# ibz_bldc_drv_revA.net
KiCad netlist of a schematic drawn in EAGLE
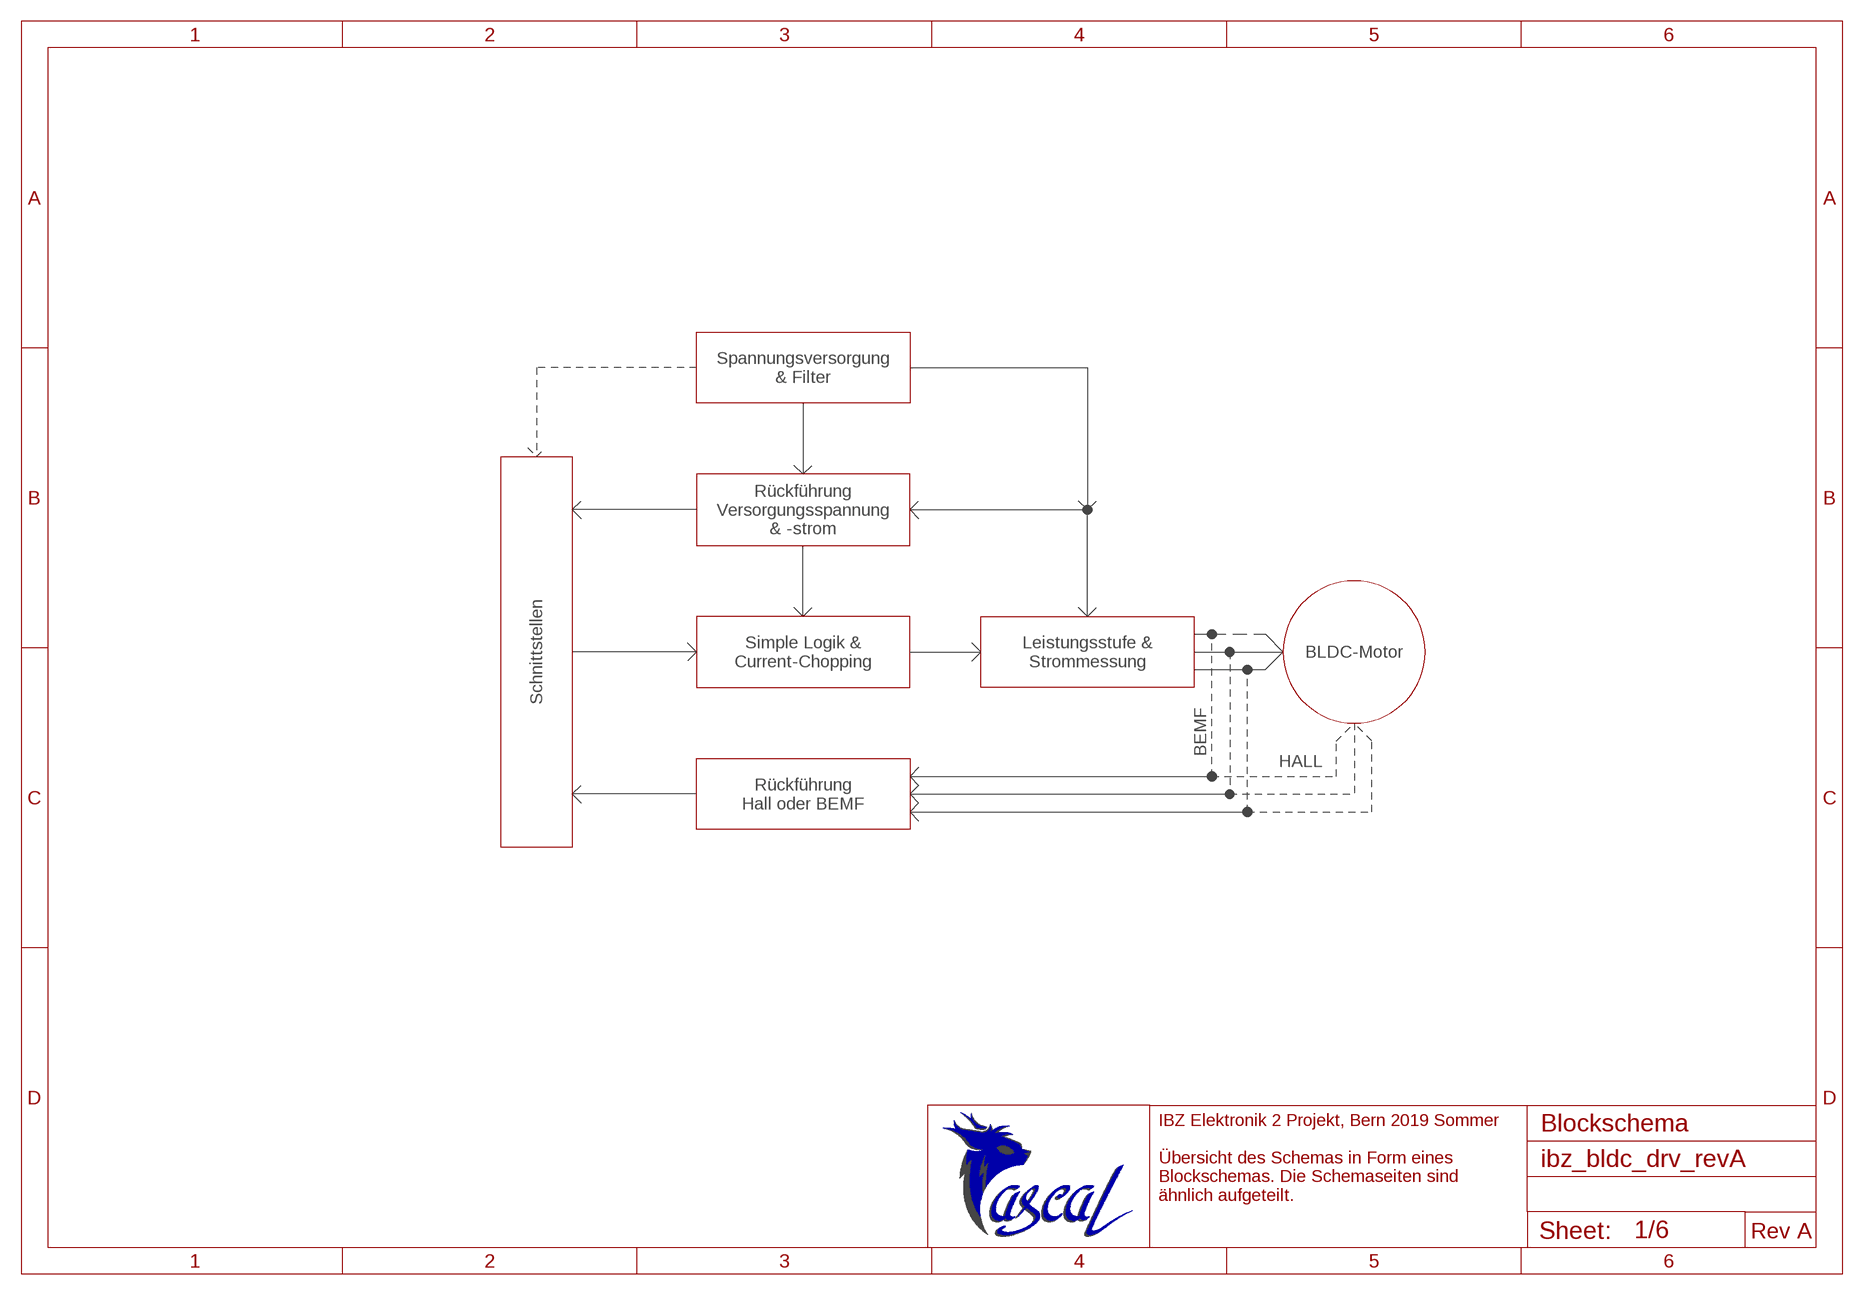
[diagram p0: schematic, sheet 1]
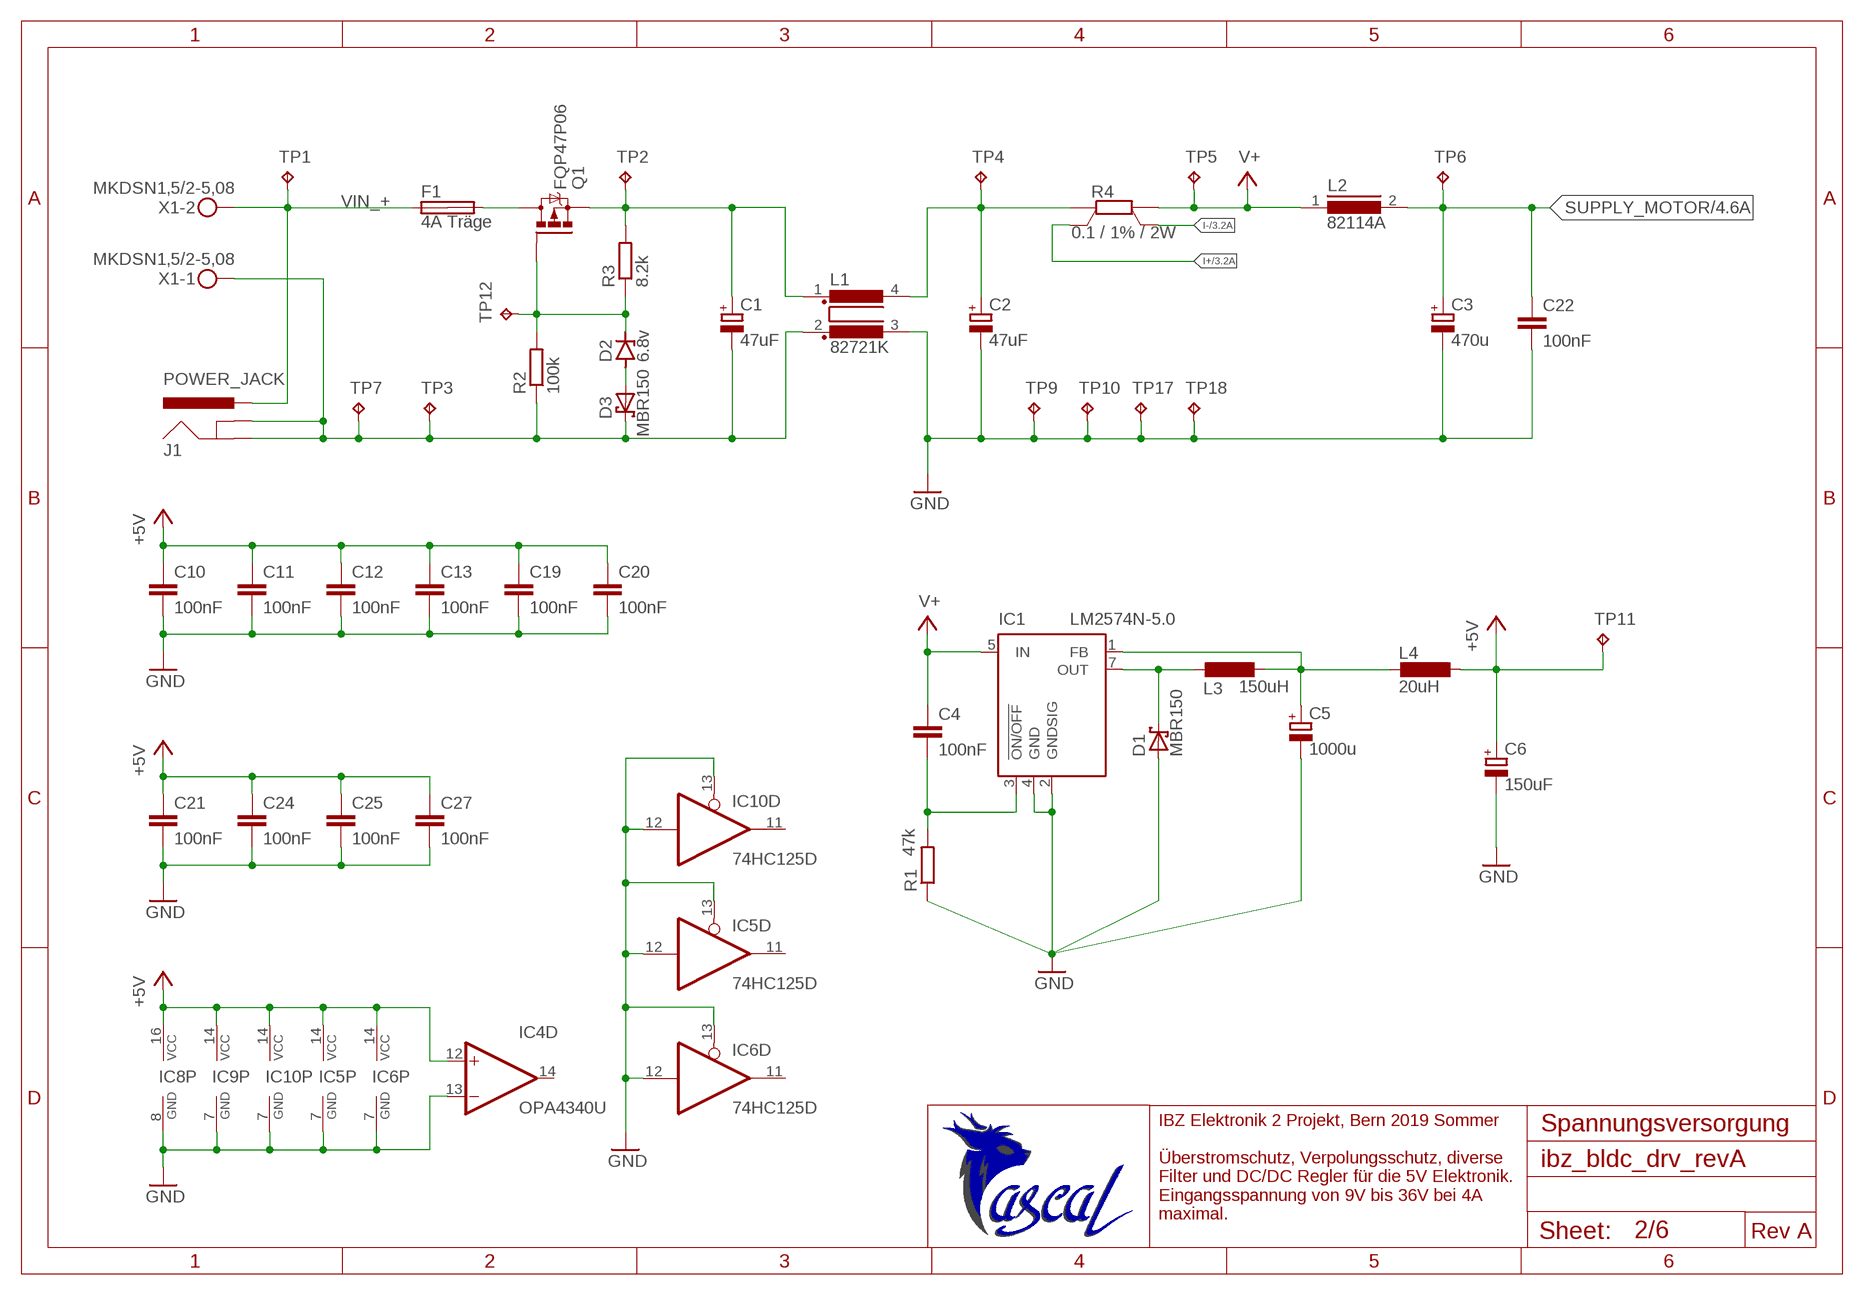
[diagram p1: schematic, sheet 2]
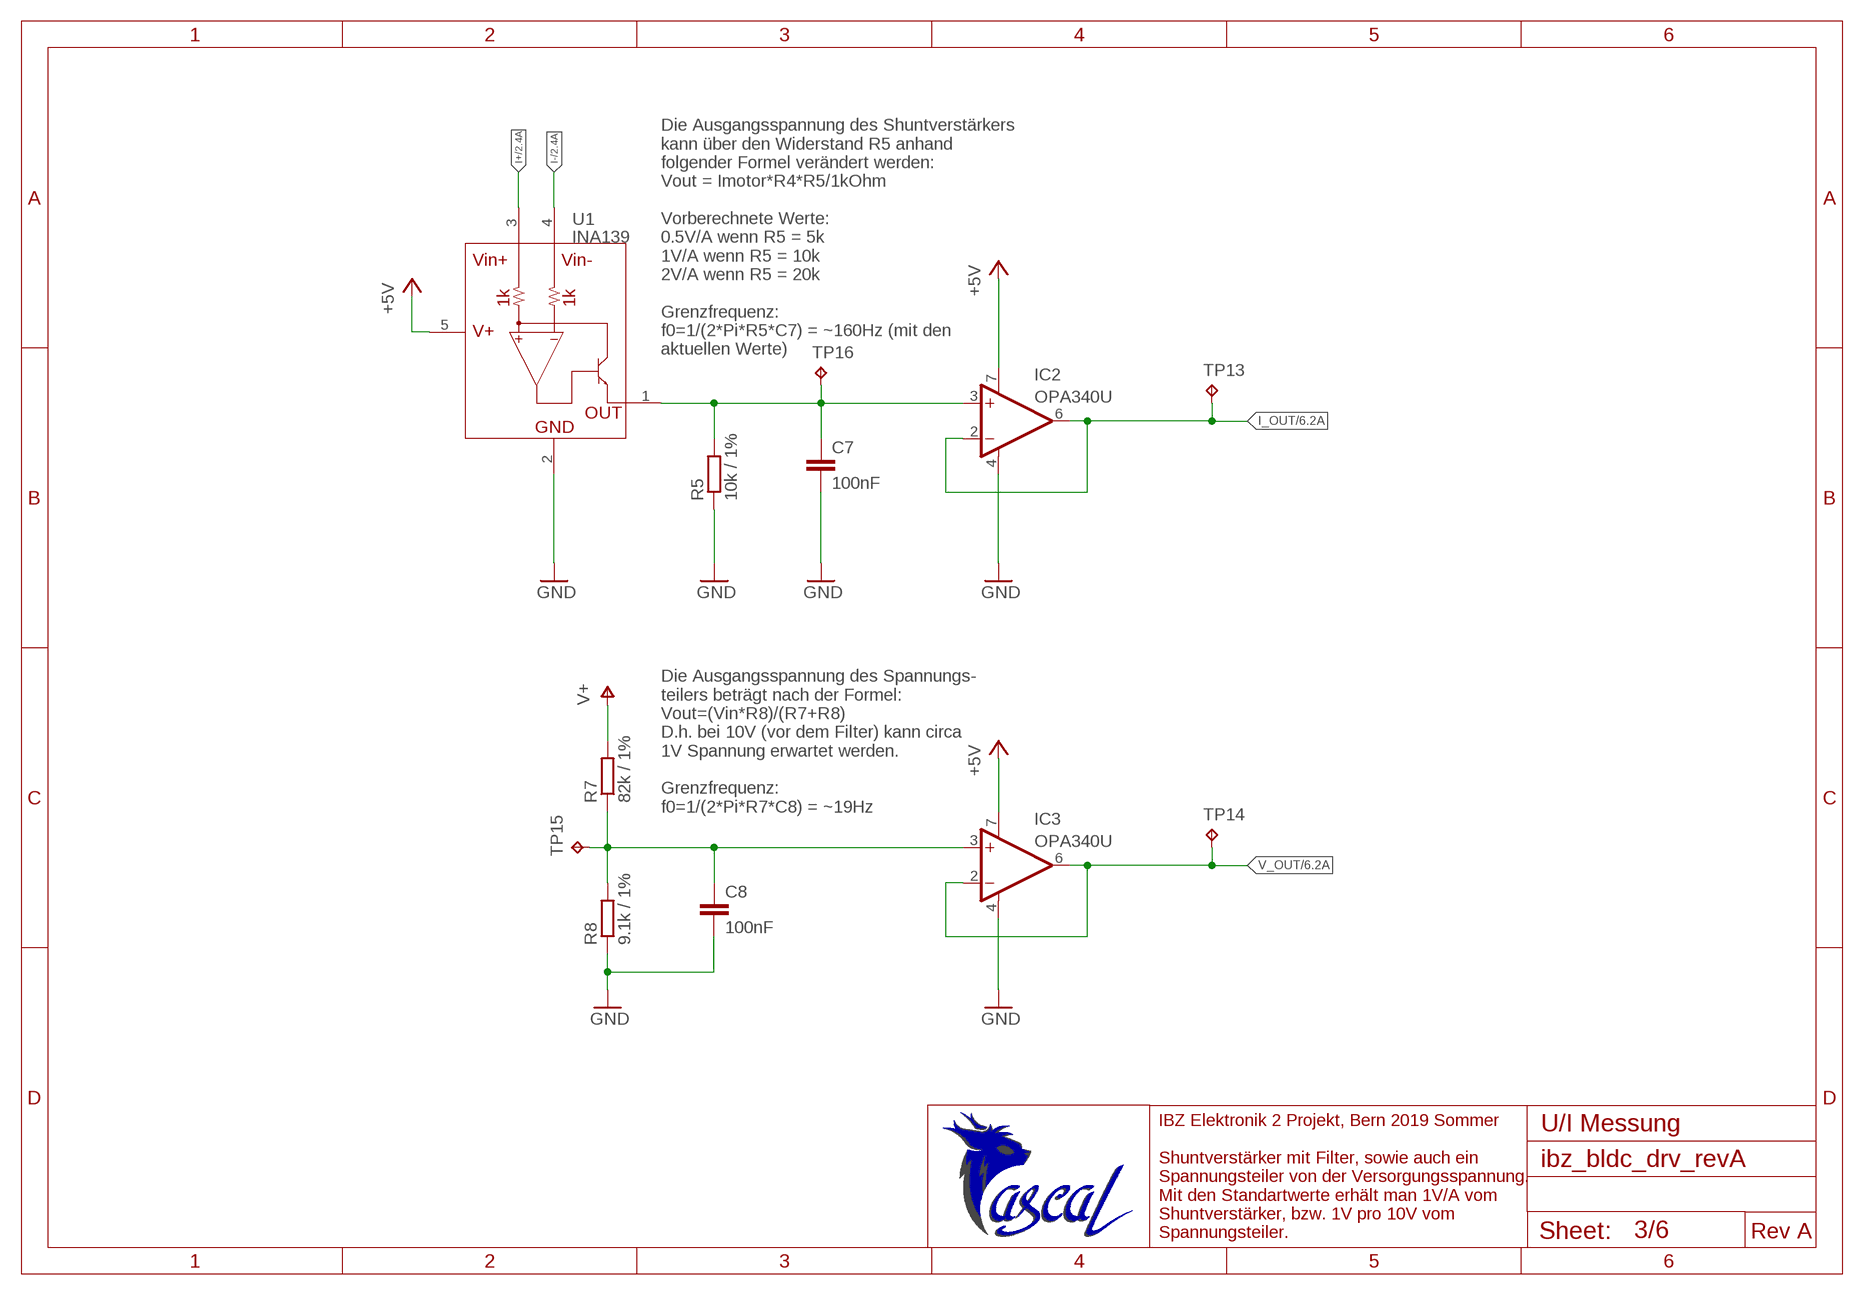
[diagram p2: schematic, sheet 3]
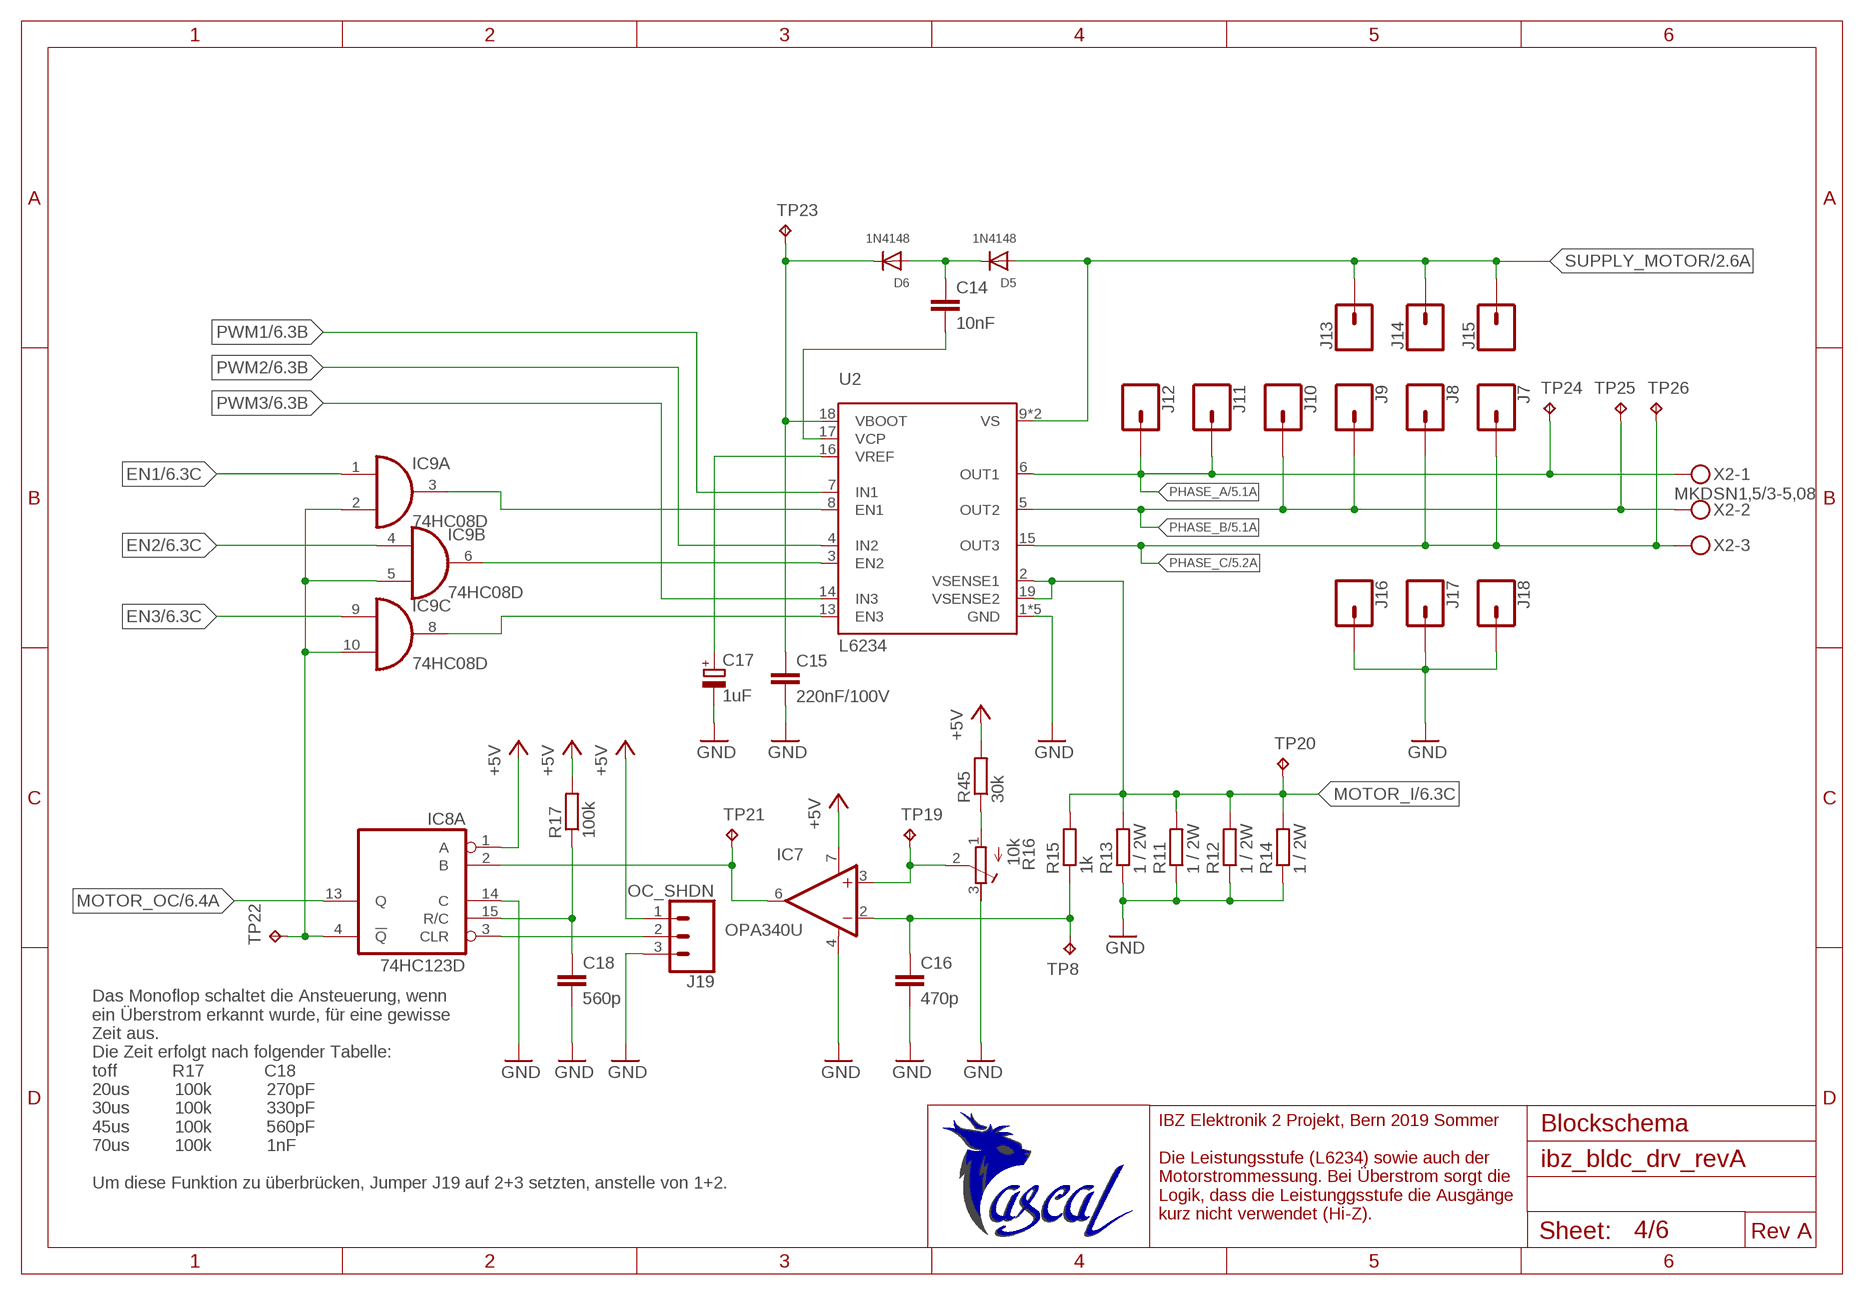
[diagram p3: schematic, sheet 4]
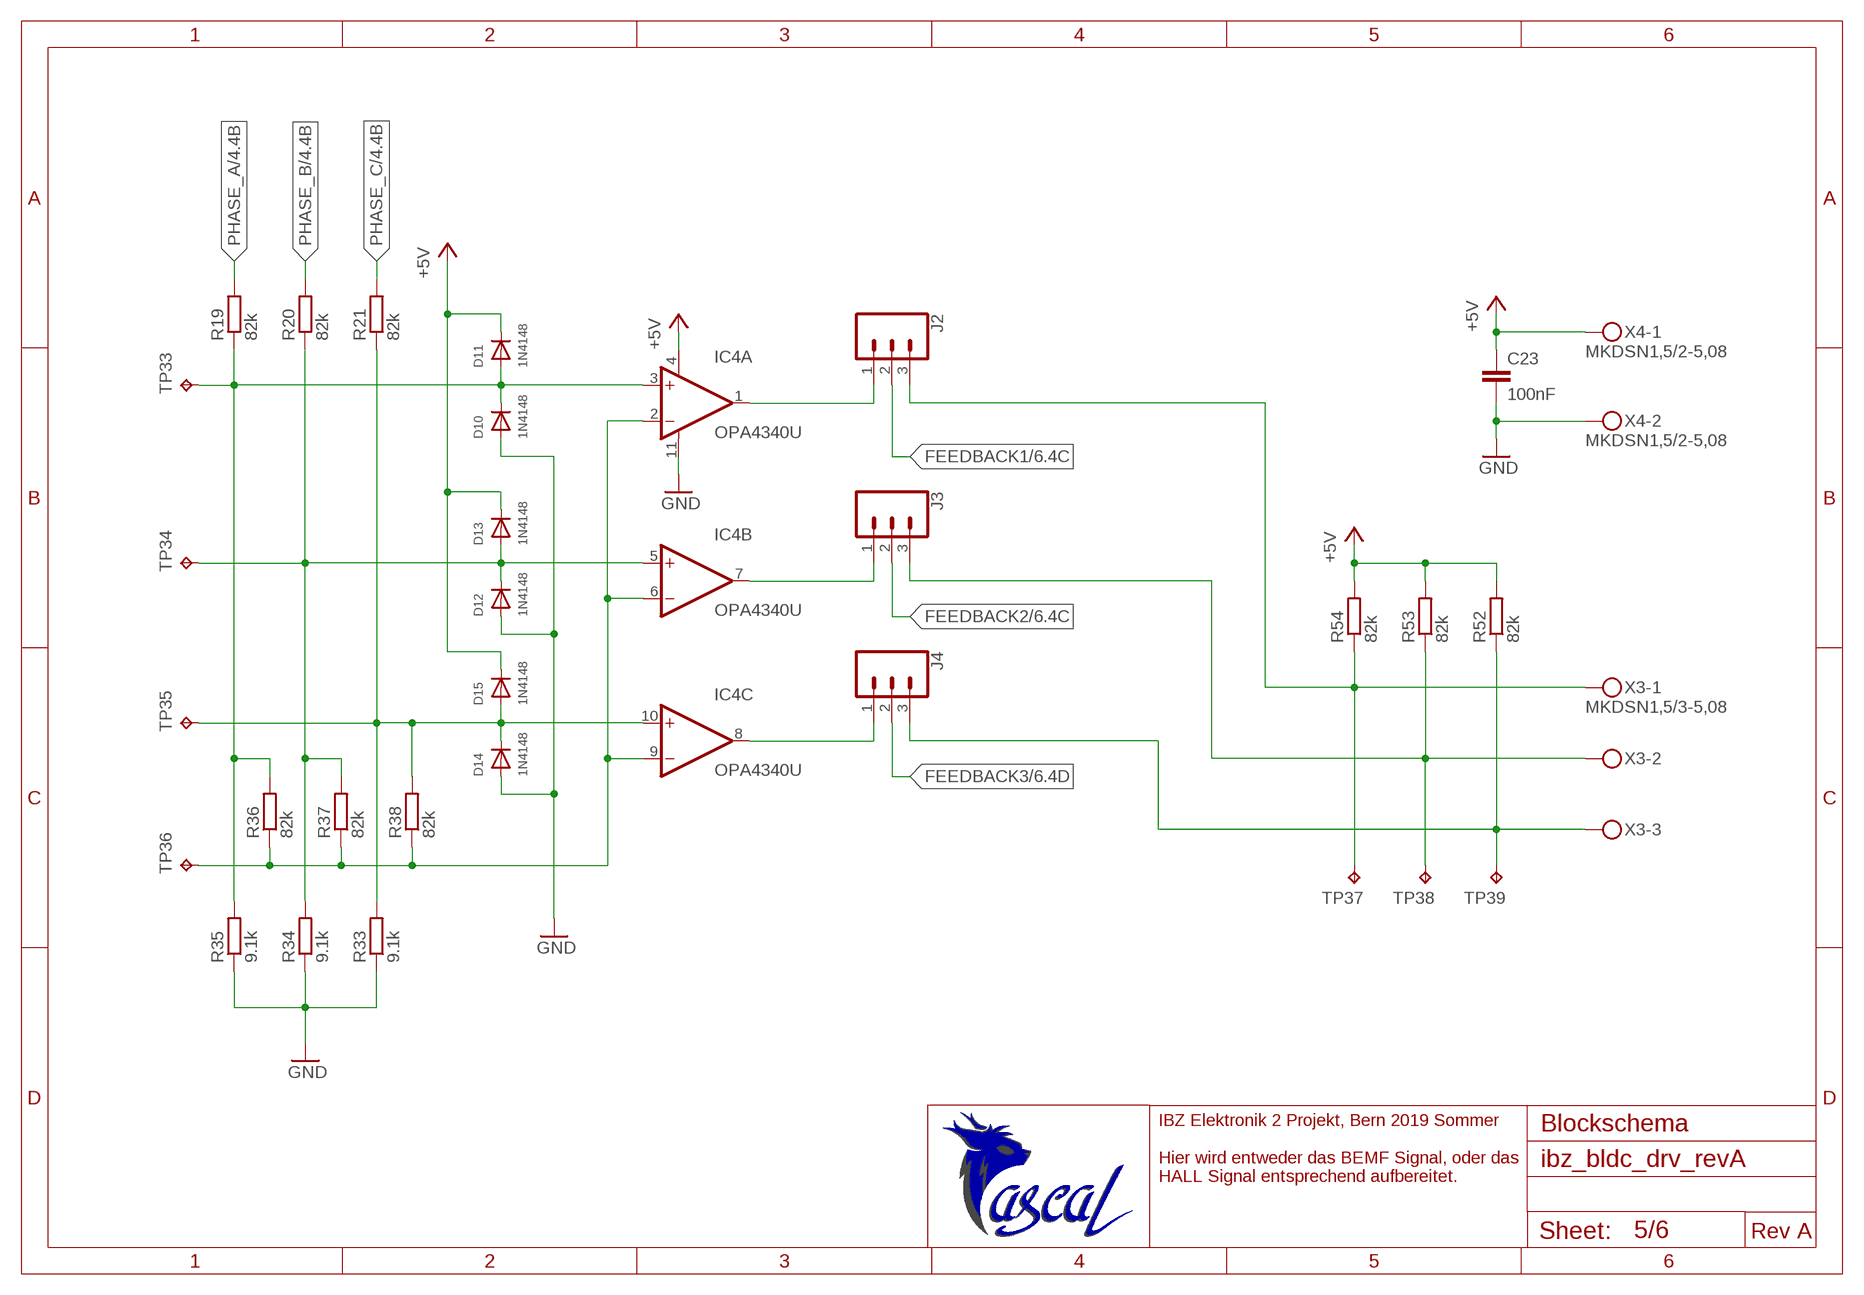
[diagram p4: schematic, sheet 5]
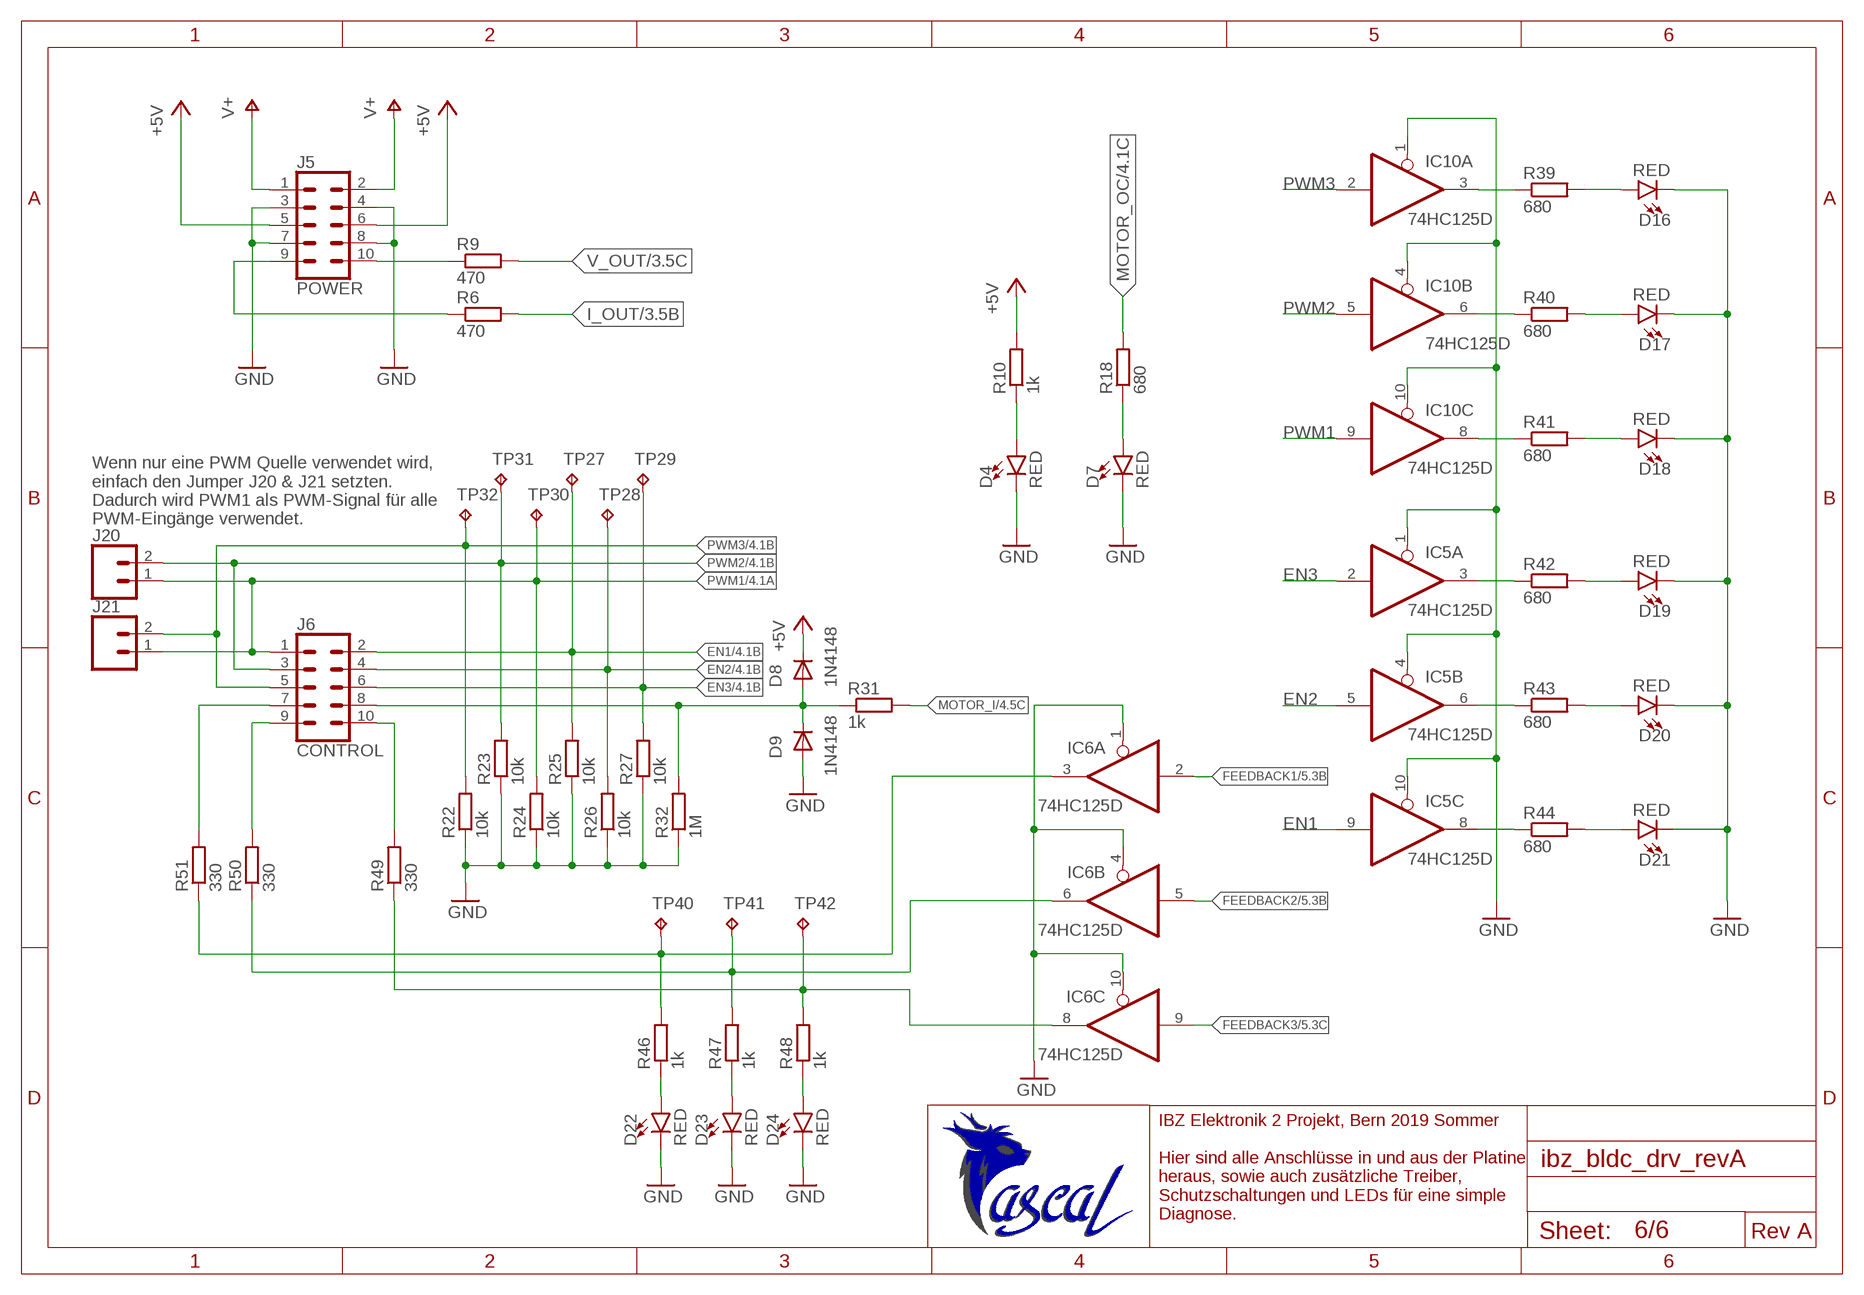
[diagram p5: schematic, sheet 6]

(export (version "E")
  (design (tool "Eeschema 10.0.6"))
  (components
    (comp (ref "C1")
      (value "47uF")
      (footprint "eagle-import:E22-9")
      (libsource (lib "eagle-import") (part "CPOL-EUE22-9AXIAL"))
    )
    (comp (ref "C2")
      (value "47uF")
      (footprint "eagle-import:E22-9")
      (libsource (lib "eagle-import") (part "CPOL-EUE22-9AXIAL"))
    )
    (comp (ref "C3")
      (value "470u")
      (footprint "eagle-import:E22-9")
      (libsource (lib "eagle-import") (part "CPOL-EUE22-9AXIAL"))
    )
    (comp (ref "C4")
      (value "100nF")
      (footprint "eagle-import:C1206")
      (libsource (lib "eagle-import") (part "C-EUC1206"))
    )
    (comp (ref "C5")
      (value "1000u")
      (footprint "eagle-import:E5-10,5")
      (libsource (lib "eagle-import") (part "CPOL-EUE5-10.5"))
    )
    (comp (ref "C6")
      (value "150uF")
      (footprint "eagle-import:153CLV-1010")
      (libsource (lib "eagle-import") (part "CPOL-EU153CLV-1010"))
    )
    (comp (ref "C10")
      (value "100nF")
      (footprint "eagle-import:C1206")
      (libsource (lib "eagle-import") (part "C-EUC1206"))
    )
    (comp (ref "C11")
      (value "100nF")
      (footprint "eagle-import:C1206")
      (libsource (lib "eagle-import") (part "C-EUC1206"))
    )
    (comp (ref "C12")
      (value "100nF")
      (footprint "eagle-import:C1206")
      (libsource (lib "eagle-import") (part "C-EUC1206"))
    )
    (comp (ref "C13")
      (value "100nF")
      (footprint "eagle-import:C1206")
      (libsource (lib "eagle-import") (part "C-EUC1206"))
    )
    (comp (ref "C19")
      (value "100nF")
      (footprint "eagle-import:C1206")
      (libsource (lib "eagle-import") (part "C-EUC1206"))
    )
    (comp (ref "C20")
      (value "100nF")
      (footprint "eagle-import:C1206")
      (libsource (lib "eagle-import") (part "C-EUC1206"))
    )
    (comp (ref "C21")
      (value "100nF")
      (footprint "eagle-import:C1206")
      (libsource (lib "eagle-import") (part "C-EUC1206"))
    )
    (comp (ref "C22")
      (value "100nF")
      (footprint "eagle-import:C1206")
      (libsource (lib "eagle-import") (part "C-EUC1206"))
    )
    (comp (ref "C24")
      (value "100nF")
      (footprint "eagle-import:C1206")
      (libsource (lib "eagle-import") (part "C-EUC1206"))
    )
    (comp (ref "C25")
      (value "100nF")
      (footprint "eagle-import:C1206")
      (libsource (lib "eagle-import") (part "C-EUC1206"))
    )
    (comp (ref "C27")
      (value "100nF")
      (footprint "eagle-import:C1206")
      (libsource (lib "eagle-import") (part "C-EUC1206"))
    )
    (comp (ref "D1")
      (value "MBR150")
      (footprint "eagle-import:DO41-7")
      (libsource (lib "eagle-import") (part "SCHOTTKY-DIODEDO41-7"))
    )
    (comp (ref "D2")
      (value "6.8v")
      (footprint "eagle-import:DO41Z10")
      (libsource (lib "eagle-import") (part "ZENER-DIODEDO41Z10"))
    )
    (comp (ref "D3")
      (value "MBR150")
      (footprint "eagle-import:DO41-7")
      (libsource (lib "eagle-import") (part "SCHOTTKY-DIODEDO41-7"))
    )
    (comp (ref "F1")
      (value "4A Träge")
      (footprint "eagle-import:SHK20Q")
      (libsource (lib "eagle-import") (part "SHK20Q"))
    )
    (comp (ref "IC1")
      (value "LM2574N-5.0")
      (footprint "eagle-import:DIL08")
      (libsource (lib "eagle-import") (part "LM2574?-N5.0"))
    )
    (comp (ref "IC4")
      (value "OPA4340U")
      (footprint "eagle-import:SO14")
      (fields (field (name "MF") "TEXAS INSTRUMENTS") (field (name "MPN") "OPA4340UA"))
      (libsource (lib "eagle-import") (part "OPA4340U"))
    )
    (comp (ref "IC5")
      (value "74HC125D")
      (footprint "eagle-import:SO14")
      (libsource (lib "eagle-import") (part "74125DHC"))
    )
    (comp (ref "IC6")
      (value "74HC125D")
      (footprint "eagle-import:SO14")
      (libsource (lib "eagle-import") (part "74125DHC"))
    )
    (comp (ref "IC8")
      (value "74HC123D")
      (footprint "eagle-import:SO16")
      (libsource (lib "eagle-import") (part "74123DLS"))
    )
    (comp (ref "IC9")
      (value "74HC08D")
      (footprint "eagle-import:SO14")
      (libsource (lib "eagle-import") (part "7408DAC"))
    )
    (comp (ref "IC10")
      (value "74HC125D")
      (footprint "eagle-import:SO14")
      (libsource (lib "eagle-import") (part "74125DAC"))
    )
    (comp (ref "J1")
      (value "POWER_JACK")
      (footprint "eagle-import:POWER_JACK_PTH")
      (libsource (lib "eagle-import") (part "POWER_JACK"))
    )
    (comp (ref "L1")
      (value "82721K")
      (footprint "eagle-import:82721K")
      (libsource (lib "eagle-import") (part "82721K"))
    )
    (comp (ref "L2")
      (value "82114A")
      (footprint "eagle-import:82114A")
      (libsource (lib "eagle-import") (part "82114A"))
    )
    (comp (ref "L3")
      (value "150uH")
      (footprint "eagle-import:IR-2")
      (libsource (lib "eagle-import") (part "L-EUIR-2"))
    )
    (comp (ref "L4")
      (value "20uH")
      (footprint "eagle-import:L5038P")
      (libsource (lib "eagle-import") (part "L-EUL5038P"))
    )
    (comp (ref "Q1")
      (value "FQP47P06")
      (footprint "eagle-import:TO220BV")
      (libsource (lib "eagle-import") (part "IRF9530"))
    )
    (comp (ref "R1")
      (value "47k")
      (footprint "eagle-import:R1206")
      (libsource (lib "eagle-import") (part "R-EU_R1206"))
    )
    (comp (ref "R2")
      (value "100k")
      (footprint "eagle-import:R1206")
      (libsource (lib "eagle-import") (part "R-EU_R1206"))
    )
    (comp (ref "R3")
      (value "8.2k")
      (footprint "eagle-import:R1206")
      (libsource (lib "eagle-import") (part "R-EU_R1206"))
    )
    (comp (ref "R4")
      (value "0.1 / 1% / 2W")
      (footprint "eagle-import:PMA-B")
      (libsource (lib "eagle-import") (part "PMA-B"))
    )
    (comp (ref "TP1")
      (value "TPPAD1-13")
      (footprint "eagle-import:P1-13")
      (libsource (lib "eagle-import") (part "TPPAD1-13"))
    )
    (comp (ref "TP2")
      (value "TPPAD1-13")
      (footprint "eagle-import:P1-13")
      (libsource (lib "eagle-import") (part "TPPAD1-13"))
    )
    (comp (ref "TP3")
      (value "TPPAD1-13")
      (footprint "eagle-import:P1-13")
      (libsource (lib "eagle-import") (part "TPPAD1-13"))
    )
    (comp (ref "TP4")
      (value "TPPAD1-13")
      (footprint "eagle-import:P1-13")
      (libsource (lib "eagle-import") (part "TPPAD1-13"))
    )
    (comp (ref "TP5")
      (value "TPPAD1-13")
      (footprint "eagle-import:P1-13")
      (libsource (lib "eagle-import") (part "TPPAD1-13"))
    )
    (comp (ref "TP6")
      (value "TPPAD1-13")
      (footprint "eagle-import:P1-13")
      (libsource (lib "eagle-import") (part "TPPAD1-13"))
    )
    (comp (ref "TP7")
      (value "TPPAD1-13")
      (footprint "eagle-import:P1-13")
      (libsource (lib "eagle-import") (part "TPPAD1-13"))
    )
    (comp (ref "TP9")
      (value "TPPAD1-13")
      (footprint "eagle-import:P1-13")
      (libsource (lib "eagle-import") (part "TPPAD1-13"))
    )
    (comp (ref "TP10")
      (value "TPPAD1-13")
      (footprint "eagle-import:P1-13")
      (libsource (lib "eagle-import") (part "TPPAD1-13"))
    )
    (comp (ref "TP11")
      (value "TPPAD1-13")
      (footprint "eagle-import:P1-13")
      (libsource (lib "eagle-import") (part "TPPAD1-13"))
    )
    (comp (ref "TP12")
      (value "TPPAD1-13")
      (footprint "eagle-import:P1-13")
      (libsource (lib "eagle-import") (part "TPPAD1-13"))
    )
    (comp (ref "TP17")
      (value "TPPAD1-13")
      (footprint "eagle-import:P1-13")
      (libsource (lib "eagle-import") (part "TPPAD1-13"))
    )
    (comp (ref "TP18")
      (value "TPPAD1-13")
      (footprint "eagle-import:P1-13")
      (libsource (lib "eagle-import") (part "TPPAD1-13"))
    )
    (comp (ref "X1")
      (value "MKDSN1,5/2-5,08")
      (footprint "eagle-import:MKDSN1,5_2-5,08")
      (libsource (lib "eagle-import") (part "MKDSN1,5/2-5,08"))
    )
    (comp (ref "C7")
      (value "100nF")
      (footprint "eagle-import:C1206")
      (libsource (lib "eagle-import") (part "C-EUC1206"))
    )
    (comp (ref "C8")
      (value "100nF")
      (footprint "eagle-import:C1206")
      (libsource (lib "eagle-import") (part "C-EUC1206"))
    )
    (comp (ref "IC2")
      (value "OPA340U")
      (footprint "eagle-import:SO08")
      (fields (field (name "MPN") "OPA340UA"))
      (libsource (lib "eagle-import") (part "OPA340U"))
    )
    (comp (ref "IC3")
      (value "OPA340U")
      (footprint "eagle-import:SO08")
      (fields (field (name "MPN") "OPA340UA"))
      (libsource (lib "eagle-import") (part "OPA340U"))
    )
    (comp (ref "R5")
      (value "10k / 1%")
      (footprint "eagle-import:R1206")
      (libsource (lib "eagle-import") (part "R-EU_R1206"))
    )
    (comp (ref "R7")
      (value "82k / 1%")
      (footprint "eagle-import:R1206")
      (libsource (lib "eagle-import") (part "R-EU_R1206"))
    )
    (comp (ref "R8")
      (value "9.1k / 1%")
      (footprint "eagle-import:R1206")
      (libsource (lib "eagle-import") (part "R-EU_R1206"))
    )
    (comp (ref "TP13")
      (value "TPPAD1-13")
      (footprint "eagle-import:P1-13")
      (libsource (lib "eagle-import") (part "TPPAD1-13"))
    )
    (comp (ref "TP14")
      (value "TPPAD1-13")
      (footprint "eagle-import:P1-13")
      (libsource (lib "eagle-import") (part "TPPAD1-13"))
    )
    (comp (ref "TP15")
      (value "TPPAD1-13")
      (footprint "eagle-import:P1-13")
      (libsource (lib "eagle-import") (part "TPPAD1-13"))
    )
    (comp (ref "TP16")
      (value "TPPAD1-13")
      (footprint "eagle-import:P1-13")
      (libsource (lib "eagle-import") (part "TPPAD1-13"))
    )
    (comp (ref "U1")
      (value "INA139")
      (footprint "eagle-import:SOT23-5")
      (libsource (lib "eagle-import") (part "INA169"))
    )
    (comp (ref "D4")
      (value "RED")
      (footprint "eagle-import:LED-1206")
      (libsource (lib "eagle-import") (part "LED-RED1206"))
    )
    (comp (ref "D7")
      (value "RED")
      (footprint "eagle-import:LED-1206")
      (libsource (lib "eagle-import") (part "LED-RED1206"))
    )
    (comp (ref "D8")
      (value "1N4148")
      (footprint "eagle-import:SMADIODE")
      (libsource (lib "eagle-import") (part "DIODESMA"))
    )
    (comp (ref "D9")
      (value "1N4148")
      (footprint "eagle-import:SMADIODE")
      (libsource (lib "eagle-import") (part "DIODESMA"))
    )
    (comp (ref "D16")
      (value "RED")
      (footprint "eagle-import:LED-1206")
      (libsource (lib "eagle-import") (part "LED-RED1206"))
    )
    (comp (ref "D17")
      (value "RED")
      (footprint "eagle-import:LED-1206")
      (libsource (lib "eagle-import") (part "LED-RED1206"))
    )
    (comp (ref "D18")
      (value "RED")
      (footprint "eagle-import:LED-1206")
      (libsource (lib "eagle-import") (part "LED-RED1206"))
    )
    (comp (ref "D19")
      (value "RED")
      (footprint "eagle-import:LED-1206")
      (libsource (lib "eagle-import") (part "LED-RED1206"))
    )
    (comp (ref "D20")
      (value "RED")
      (footprint "eagle-import:LED-1206")
      (libsource (lib "eagle-import") (part "LED-RED1206"))
    )
    (comp (ref "D21")
      (value "RED")
      (footprint "eagle-import:LED-1206")
      (libsource (lib "eagle-import") (part "LED-RED1206"))
    )
    (comp (ref "D22")
      (value "RED")
      (footprint "eagle-import:LED-1206")
      (libsource (lib "eagle-import") (part "LED-RED1206"))
    )
    (comp (ref "D23")
      (value "RED")
      (footprint "eagle-import:LED-1206")
      (libsource (lib "eagle-import") (part "LED-RED1206"))
    )
    (comp (ref "D24")
      (value "RED")
      (footprint "eagle-import:LED-1206")
      (libsource (lib "eagle-import") (part "LED-RED1206"))
    )
    (comp (ref "J5")
      (value "POWER")
      (footprint "eagle-import:2X5-SHROUDED")
      (libsource (lib "eagle-import") (part "CONN_05X2SHD"))
    )
    (comp (ref "J6")
      (value "CONTROL")
      (footprint "eagle-import:2X5-SHROUDED")
      (libsource (lib "eagle-import") (part "CONN_05X2SHD"))
    )
    (comp (ref "J20")
      (value "CONN_02")
      (footprint "eagle-import:1X02")
      (libsource (lib "eagle-import") (part "CONN_02"))
    )
    (comp (ref "J21")
      (value "CONN_02")
      (footprint "eagle-import:1X02")
      (libsource (lib "eagle-import") (part "CONN_02"))
    )
    (comp (ref "R6")
      (value "470")
      (footprint "eagle-import:M1206")
      (libsource (lib "eagle-import") (part "R-EU_M1206"))
    )
    (comp (ref "R9")
      (value "470")
      (footprint "eagle-import:M1206")
      (libsource (lib "eagle-import") (part "R-EU_M1206"))
    )
    (comp (ref "R10")
      (value "1k")
      (footprint "eagle-import:R1206")
      (libsource (lib "eagle-import") (part "R-EU_R1206"))
    )
    (comp (ref "R18")
      (value "680")
      (footprint "eagle-import:R1206")
      (libsource (lib "eagle-import") (part "R-EU_R1206"))
    )
    (comp (ref "R22")
      (value "10k")
      (footprint "eagle-import:R1206")
      (libsource (lib "eagle-import") (part "R-EU_R1206"))
    )
    (comp (ref "R23")
      (value "10k")
      (footprint "eagle-import:R1206")
      (libsource (lib "eagle-import") (part "R-EU_R1206"))
    )
    (comp (ref "R24")
      (value "10k")
      (footprint "eagle-import:R1206")
      (libsource (lib "eagle-import") (part "R-EU_R1206"))
    )
    (comp (ref "R25")
      (value "10k")
      (footprint "eagle-import:R1206")
      (libsource (lib "eagle-import") (part "R-EU_R1206"))
    )
    (comp (ref "R26")
      (value "10k")
      (footprint "eagle-import:R1206")
      (libsource (lib "eagle-import") (part "R-EU_R1206"))
    )
    (comp (ref "R27")
      (value "10k")
      (footprint "eagle-import:R1206")
      (libsource (lib "eagle-import") (part "R-EU_R1206"))
    )
    (comp (ref "R31")
      (value "1k")
      (footprint "eagle-import:R1206")
      (libsource (lib "eagle-import") (part "R-EU_R1206"))
    )
    (comp (ref "R32")
      (value "1M")
      (footprint "eagle-import:R1206")
      (libsource (lib "eagle-import") (part "R-EU_R1206"))
    )
    (comp (ref "R39")
      (value "680")
      (footprint "eagle-import:R1206")
      (libsource (lib "eagle-import") (part "R-EU_R1206"))
    )
    (comp (ref "R40")
      (value "680")
      (footprint "eagle-import:R1206")
      (libsource (lib "eagle-import") (part "R-EU_R1206"))
    )
    (comp (ref "R41")
      (value "680")
      (footprint "eagle-import:R1206")
      (libsource (lib "eagle-import") (part "R-EU_R1206"))
    )
    (comp (ref "R42")
      (value "680")
      (footprint "eagle-import:R1206")
      (libsource (lib "eagle-import") (part "R-EU_R1206"))
    )
    (comp (ref "R43")
      (value "680")
      (footprint "eagle-import:R1206")
      (libsource (lib "eagle-import") (part "R-EU_R1206"))
    )
    (comp (ref "R44")
      (value "680")
      (footprint "eagle-import:R1206")
      (libsource (lib "eagle-import") (part "R-EU_R1206"))
    )
    (comp (ref "R46")
      (value "1k")
      (footprint "eagle-import:R1206")
      (libsource (lib "eagle-import") (part "R-EU_R1206"))
    )
    (comp (ref "R47")
      (value "1k")
      (footprint "eagle-import:R1206")
      (libsource (lib "eagle-import") (part "R-EU_R1206"))
    )
    (comp (ref "R48")
      (value "1k")
      (footprint "eagle-import:R1206")
      (libsource (lib "eagle-import") (part "R-EU_R1206"))
    )
    (comp (ref "R49")
      (value "330")
      (footprint "eagle-import:R1206")
      (libsource (lib "eagle-import") (part "R-EU_R1206"))
    )
    (comp (ref "R50")
      (value "330")
      (footprint "eagle-import:R1206")
      (libsource (lib "eagle-import") (part "R-EU_R1206"))
    )
    (comp (ref "R51")
      (value "330")
      (footprint "eagle-import:R1206")
      (libsource (lib "eagle-import") (part "R-EU_R1206"))
    )
    (comp (ref "TP27")
      (value "TPPAD1-13")
      (footprint "eagle-import:P1-13")
      (libsource (lib "eagle-import") (part "TPPAD1-13"))
    )
    (comp (ref "TP28")
      (value "TPPAD1-13")
      (footprint "eagle-import:P1-13")
      (libsource (lib "eagle-import") (part "TPPAD1-13"))
    )
    (comp (ref "TP29")
      (value "TPPAD1-13")
      (footprint "eagle-import:P1-13")
      (libsource (lib "eagle-import") (part "TPPAD1-13"))
    )
    (comp (ref "TP30")
      (value "TPPAD1-13")
      (footprint "eagle-import:P1-13")
      (libsource (lib "eagle-import") (part "TPPAD1-13"))
    )
    (comp (ref "TP31")
      (value "TPPAD1-13")
      (footprint "eagle-import:P1-13")
      (libsource (lib "eagle-import") (part "TPPAD1-13"))
    )
    (comp (ref "TP32")
      (value "TPPAD1-13")
      (footprint "eagle-import:P1-13")
      (libsource (lib "eagle-import") (part "TPPAD1-13"))
    )
    (comp (ref "TP40")
      (value "TPPAD1-13")
      (footprint "eagle-import:P1-13")
      (libsource (lib "eagle-import") (part "TPPAD1-13"))
    )
    (comp (ref "TP41")
      (value "TPPAD1-13")
      (footprint "eagle-import:P1-13")
      (libsource (lib "eagle-import") (part "TPPAD1-13"))
    )
    (comp (ref "TP42")
      (value "TPPAD1-13")
      (footprint "eagle-import:P1-13")
      (libsource (lib "eagle-import") (part "TPPAD1-13"))
    )
    (comp (ref "C23")
      (value "100nF")
      (footprint "eagle-import:C1206")
      (libsource (lib "eagle-import") (part "C-EUC1206"))
    )
    (comp (ref "D10")
      (value "1N4148")
      (footprint "eagle-import:SMADIODE")
      (libsource (lib "eagle-import") (part "DIODESMA"))
    )
    (comp (ref "D11")
      (value "1N4148")
      (footprint "eagle-import:SMADIODE")
      (libsource (lib "eagle-import") (part "DIODESMA"))
    )
    (comp (ref "D12")
      (value "1N4148")
      (footprint "eagle-import:SMADIODE")
      (libsource (lib "eagle-import") (part "DIODESMA"))
    )
    (comp (ref "D13")
      (value "1N4148")
      (footprint "eagle-import:SMADIODE")
      (libsource (lib "eagle-import") (part "DIODESMA"))
    )
    (comp (ref "D14")
      (value "1N4148")
      (footprint "eagle-import:SMADIODE")
      (libsource (lib "eagle-import") (part "DIODESMA"))
    )
    (comp (ref "D15")
      (value "1N4148")
      (footprint "eagle-import:SMADIODE")
      (libsource (lib "eagle-import") (part "DIODESMA"))
    )
    (comp (ref "J2")
      (value "CONN_03")
      (footprint "eagle-import:1X03")
      (libsource (lib "eagle-import") (part "CONN_03"))
    )
    (comp (ref "J3")
      (value "CONN_03")
      (footprint "eagle-import:1X03")
      (libsource (lib "eagle-import") (part "CONN_03"))
    )
    (comp (ref "J4")
      (value "CONN_03")
      (footprint "eagle-import:1X03")
      (libsource (lib "eagle-import") (part "CONN_03"))
    )
    (comp (ref "R19")
      (value "82k")
      (footprint "eagle-import:R1206")
      (libsource (lib "eagle-import") (part "R-EU_R1206"))
    )
    (comp (ref "R20")
      (value "82k")
      (footprint "eagle-import:R1206")
      (libsource (lib "eagle-import") (part "R-EU_R1206"))
    )
    (comp (ref "R21")
      (value "82k")
      (footprint "eagle-import:R1206")
      (libsource (lib "eagle-import") (part "R-EU_R1206"))
    )
    (comp (ref "R33")
      (value "9.1k")
      (footprint "eagle-import:R1206")
      (libsource (lib "eagle-import") (part "R-EU_R1206"))
    )
    (comp (ref "R34")
      (value "9.1k")
      (footprint "eagle-import:R1206")
      (libsource (lib "eagle-import") (part "R-EU_R1206"))
    )
    (comp (ref "R35")
      (value "9.1k")
      (footprint "eagle-import:R1206")
      (libsource (lib "eagle-import") (part "R-EU_R1206"))
    )
    (comp (ref "R36")
      (value "82k")
      (footprint "eagle-import:R1206")
      (libsource (lib "eagle-import") (part "R-EU_R1206"))
    )
    (comp (ref "R37")
      (value "82k")
      (footprint "eagle-import:R1206")
      (libsource (lib "eagle-import") (part "R-EU_R1206"))
    )
    (comp (ref "R38")
      (value "82k")
      (footprint "eagle-import:R1206")
      (libsource (lib "eagle-import") (part "R-EU_R1206"))
    )
    (comp (ref "R52")
      (value "82k")
      (footprint "eagle-import:R1206")
      (libsource (lib "eagle-import") (part "R-EU_R1206"))
    )
    (comp (ref "R53")
      (value "82k")
      (footprint "eagle-import:R1206")
      (libsource (lib "eagle-import") (part "R-EU_R1206"))
    )
    (comp (ref "R54")
      (value "82k")
      (footprint "eagle-import:R1206")
      (libsource (lib "eagle-import") (part "R-EU_R1206"))
    )
    (comp (ref "TP33")
      (value "TPPAD1-13")
      (footprint "eagle-import:P1-13")
      (libsource (lib "eagle-import") (part "TPPAD1-13"))
    )
    (comp (ref "TP34")
      (value "TPPAD1-13")
      (footprint "eagle-import:P1-13")
      (libsource (lib "eagle-import") (part "TPPAD1-13"))
    )
    (comp (ref "TP35")
      (value "TPPAD1-13")
      (footprint "eagle-import:P1-13")
      (libsource (lib "eagle-import") (part "TPPAD1-13"))
    )
    (comp (ref "TP36")
      (value "TPPAD1-13")
      (footprint "eagle-import:P1-13")
      (libsource (lib "eagle-import") (part "TPPAD1-13"))
    )
    (comp (ref "TP37")
      (value "TPPAD1-13")
      (footprint "eagle-import:P1-13")
      (libsource (lib "eagle-import") (part "TPPAD1-13"))
    )
    (comp (ref "TP38")
      (value "TPPAD1-13")
      (footprint "eagle-import:P1-13")
      (libsource (lib "eagle-import") (part "TPPAD1-13"))
    )
    (comp (ref "TP39")
      (value "TPPAD1-13")
      (footprint "eagle-import:P1-13")
      (libsource (lib "eagle-import") (part "TPPAD1-13"))
    )
    (comp (ref "X3")
      (value "MKDSN1,5/3-5,08")
      (footprint "eagle-import:MKDSN1,5_3-5,08")
      (libsource (lib "eagle-import") (part "MKDSN1,5/3-5,08"))
    )
    (comp (ref "X4")
      (value "MKDSN1,5/2-5,08")
      (footprint "eagle-import:MKDSN1,5_2-5,08")
      (libsource (lib "eagle-import") (part "MKDSN1,5/2-5,08"))
    )
    (comp (ref "C14")
      (value "10nF")
      (footprint "eagle-import:C1206")
      (libsource (lib "eagle-import") (part "C-EUC1206"))
    )
    (comp (ref "C15")
      (value "220nF/100V")
      (footprint "eagle-import:C1206")
      (libsource (lib "eagle-import") (part "C-EUC1206"))
    )
    (comp (ref "C16")
      (value "470p")
      (footprint "eagle-import:C1206")
      (libsource (lib "eagle-import") (part "C-EUC1206"))
    )
    (comp (ref "C17")
      (value "1uF")
      (footprint "eagle-import:153CLV-0505")
      (libsource (lib "eagle-import") (part "CPOL-EU153CLV-0505"))
    )
    (comp (ref "C18")
      (value "560p")
      (footprint "eagle-import:C1206")
      (libsource (lib "eagle-import") (part "C-EUC1206"))
    )
    (comp (ref "D5")
      (value "1N4148")
      (footprint "eagle-import:SMADIODE")
      (libsource (lib "eagle-import") (part "DIODESMA"))
    )
    (comp (ref "D6")
      (value "1N4148")
      (footprint "eagle-import:SMADIODE")
      (libsource (lib "eagle-import") (part "DIODESMA"))
    )
    (comp (ref "IC7")
      (value "OPA340U")
      (footprint "eagle-import:SO08")
      (fields (field (name "MPN") "OPA340UA"))
      (libsource (lib "eagle-import") (part "OPA340U"))
    )
    (comp (ref "J7")
      (value "CONN_01PTH_2MM")
      (footprint "eagle-import:1X01_2MM")
      (libsource (lib "eagle-import") (part "CONN_01PTH_2MM"))
    )
    (comp (ref "J8")
      (value "CONN_01PTH_2MM")
      (footprint "eagle-import:1X01_2MM")
      (libsource (lib "eagle-import") (part "CONN_01PTH_2MM"))
    )
    (comp (ref "J9")
      (value "CONN_01PTH_2MM")
      (footprint "eagle-import:1X01_2MM")
      (libsource (lib "eagle-import") (part "CONN_01PTH_2MM"))
    )
    (comp (ref "J10")
      (value "CONN_01PTH_2MM")
      (footprint "eagle-import:1X01_2MM")
      (libsource (lib "eagle-import") (part "CONN_01PTH_2MM"))
    )
    (comp (ref "J11")
      (value "CONN_01PTH_2MM")
      (footprint "eagle-import:1X01_2MM")
      (libsource (lib "eagle-import") (part "CONN_01PTH_2MM"))
    )
    (comp (ref "J12")
      (value "CONN_01PTH_2MM")
      (footprint "eagle-import:1X01_2MM")
      (libsource (lib "eagle-import") (part "CONN_01PTH_2MM"))
    )
    (comp (ref "J13")
      (value "CONN_01PTH_2MM")
      (footprint "eagle-import:1X01_2MM")
      (libsource (lib "eagle-import") (part "CONN_01PTH_2MM"))
    )
    (comp (ref "J14")
      (value "CONN_01PTH_2MM")
      (footprint "eagle-import:1X01_2MM")
      (libsource (lib "eagle-import") (part "CONN_01PTH_2MM"))
    )
    (comp (ref "J15")
      (value "CONN_01PTH_2MM")
      (footprint "eagle-import:1X01_2MM")
      (libsource (lib "eagle-import") (part "CONN_01PTH_2MM"))
    )
    (comp (ref "J16")
      (value "CONN_01PTH_2MM")
      (footprint "eagle-import:1X01_2MM")
      (libsource (lib "eagle-import") (part "CONN_01PTH_2MM"))
    )
    (comp (ref "J17")
      (value "CONN_01PTH_2MM")
      (footprint "eagle-import:1X01_2MM")
      (libsource (lib "eagle-import") (part "CONN_01PTH_2MM"))
    )
    (comp (ref "J18")
      (value "CONN_01PTH_2MM")
      (footprint "eagle-import:1X01_2MM")
      (libsource (lib "eagle-import") (part "CONN_01PTH_2MM"))
    )
    (comp (ref "J19")
      (value "OC_SHDN")
      (footprint "eagle-import:1X03")
      (libsource (lib "eagle-import") (part "CONN_03"))
    )
    (comp (ref "R11")
      (value "1 / 2W")
      (footprint "eagle-import:0411_15")
      (libsource (lib "eagle-import") (part "R-EU_0411/15"))
    )
    (comp (ref "R12")
      (value "1 / 2W")
      (footprint "eagle-import:0411_15")
      (libsource (lib "eagle-import") (part "R-EU_0411/15"))
    )
    (comp (ref "R13")
      (value "1 / 2W")
      (footprint "eagle-import:0411_15")
      (libsource (lib "eagle-import") (part "R-EU_0411/15"))
    )
    (comp (ref "R14")
      (value "1 / 2W")
      (footprint "eagle-import:0411_15")
      (libsource (lib "eagle-import") (part "R-EU_0411/15"))
    )
    (comp (ref "R15")
      (value "1k")
      (footprint "eagle-import:R1206")
      (libsource (lib "eagle-import") (part "R-EU_R1206"))
    )
    (comp (ref "R16")
      (value "10k")
      (footprint "eagle-import:RTRIM64W")
      (libsource (lib "eagle-import") (part "R-TRIMM64W"))
    )
    (comp (ref "R17")
      (value "100k")
      (footprint "eagle-import:R1206")
      (libsource (lib "eagle-import") (part "R-EU_R1206"))
    )
    (comp (ref "R45")
      (value "30k")
      (footprint "eagle-import:R1206")
      (libsource (lib "eagle-import") (part "R-EU_R1206"))
    )
    (comp (ref "TP8")
      (value "TPPAD1-13")
      (footprint "eagle-import:P1-13")
      (libsource (lib "eagle-import") (part "TPPAD1-13"))
    )
    (comp (ref "TP19")
      (value "TPPAD1-13")
      (footprint "eagle-import:P1-13")
      (libsource (lib "eagle-import") (part "TPPAD1-13"))
    )
    (comp (ref "TP20")
      (value "TPPAD1-13")
      (footprint "eagle-import:P1-13")
      (libsource (lib "eagle-import") (part "TPPAD1-13"))
    )
    (comp (ref "TP21")
      (value "TPPAD1-13")
      (footprint "eagle-import:P1-13")
      (libsource (lib "eagle-import") (part "TPPAD1-13"))
    )
    (comp (ref "TP22")
      (value "TPPAD1-13")
      (footprint "eagle-import:P1-13")
      (libsource (lib "eagle-import") (part "TPPAD1-13"))
    )
    (comp (ref "TP23")
      (value "TPPAD1-13")
      (footprint "eagle-import:P1-13")
      (libsource (lib "eagle-import") (part "TPPAD1-13"))
    )
    (comp (ref "TP24")
      (value "TPPAD1-13")
      (footprint "eagle-import:P1-13")
      (libsource (lib "eagle-import") (part "TPPAD1-13"))
    )
    (comp (ref "TP25")
      (value "TPPAD1-13")
      (footprint "eagle-import:P1-13")
      (libsource (lib "eagle-import") (part "TPPAD1-13"))
    )
    (comp (ref "TP26")
      (value "TPPAD1-13")
      (footprint "eagle-import:P1-13")
      (libsource (lib "eagle-import") (part "TPPAD1-13"))
    )
    (comp (ref "U2")
      (value "L6234")
      (footprint "eagle-import:POWERSO20")
      (libsource (lib "eagle-import") (part "L6234"))
    )
    (comp (ref "X2")
      (value "MKDSN1,5/3-5,08")
      (footprint "eagle-import:MKDSN1,5_3-5,08")
      (libsource (lib "eagle-import") (part "MKDSN1,5/3-5,08"))
    )
  )
  (nets
    (net (code "1") (name "+5V") (class "Default")
      (node (ref "C10") (pin "1") (pinfunction "1_1") (pintype "passive"))
      (node (ref "C11") (pin "1") (pinfunction "1_1") (pintype "passive"))
      (node (ref "C12") (pin "1") (pinfunction "1_1") (pintype "passive"))
      (node (ref "C13") (pin "1") (pinfunction "1_1") (pintype "passive"))
      (node (ref "C19") (pin "1") (pinfunction "1_1") (pintype "passive"))
      (node (ref "C20") (pin "1") (pinfunction "1_1") (pintype "passive"))
      (node (ref "C21") (pin "1") (pinfunction "1_1") (pintype "passive"))
      (node (ref "C23") (pin "1") (pinfunction "1_1") (pintype "passive"))
      (node (ref "C24") (pin "1") (pinfunction "1_1") (pintype "passive"))
      (node (ref "C25") (pin "1") (pinfunction "1_1") (pintype "passive"))
      (node (ref "C27") (pin "1") (pinfunction "1_1") (pintype "passive"))
      (node (ref "C6") (pin "+") (pinfunction "+_+") (pintype "passive"))
      (node (ref "D11") (pin "C") (pinfunction "C_C") (pintype "passive"))
      (node (ref "D13") (pin "C") (pinfunction "C_C") (pintype "passive"))
      (node (ref "D15") (pin "C") (pinfunction "C_C") (pintype "passive"))
      (node (ref "D8") (pin "C") (pinfunction "C_C") (pintype "passive"))
      (node (ref "IC10") (pin "14") (pinfunction "VCC_14") (pintype "power_in"))
      (node (ref "IC2") (pin "7") (pinfunction "V+_7") (pintype "power_in"))
      (node (ref "IC3") (pin "7") (pinfunction "V+_7") (pintype "power_in"))
      (node (ref "IC4") (pin "12") (pinfunction "+IN_12") (pintype "input"))
      (node (ref "IC4") (pin "4") (pinfunction "V+_4") (pintype "power_in"))
      (node (ref "IC5") (pin "14") (pinfunction "VCC_14") (pintype "power_in"))
      (node (ref "IC6") (pin "14") (pinfunction "VCC_14") (pintype "power_in"))
      (node (ref "IC7") (pin "7") (pinfunction "V+_7") (pintype "power_in"))
      (node (ref "IC8") (pin "1") (pinfunction "A_1") (pintype "input"))
      (node (ref "IC8") (pin "16") (pinfunction "VCC_16") (pintype "power_in"))
      (node (ref "IC9") (pin "14") (pinfunction "VCC_14") (pintype "power_in"))
      (node (ref "J19") (pin "1") (pinfunction "1_1") (pintype "passive"))
      (node (ref "J5") (pin "5") (pinfunction "5_5") (pintype "passive"))
      (node (ref "J5") (pin "6") (pinfunction "6_6") (pintype "passive"))
      (node (ref "L4") (pin "1") (pinfunction "1_1") (pintype "passive"))
      (node (ref "R10") (pin "2") (pinfunction "2_2") (pintype "passive"))
      (node (ref "R17") (pin "2") (pinfunction "2_2") (pintype "passive"))
      (node (ref "R45") (pin "2") (pinfunction "2_2") (pintype "passive"))
      (node (ref "R52") (pin "2") (pinfunction "2_2") (pintype "passive"))
      (node (ref "R53") (pin "2") (pinfunction "2_2") (pintype "passive"))
      (node (ref "R54") (pin "2") (pinfunction "2_2") (pintype "passive"))
      (node (ref "TP11") (pin "TP") (pinfunction "TP_TP") (pintype "input"))
      (node (ref "U1") (pin "5") (pinfunction "V+_5") (pintype "bidirectional"))
      (node (ref "X4") (pin "1") (pinfunction "KL_1") (pintype "passive"))
    )
    (net (code "2") (name "EN1") (class "Default")
      (node (ref "IC5") (pin "9") (pinfunction "I_9") (pintype "input"))
      (node (ref "IC9") (pin "1") (pinfunction "I0_1") (pintype "input"))
      (node (ref "J6") (pin "2") (pinfunction "2_2") (pintype "passive"))
      (node (ref "R25") (pin "2") (pinfunction "2_2") (pintype "passive"))
      (node (ref "TP27") (pin "TP") (pinfunction "TP_TP") (pintype "input"))
    )
    (net (code "3") (name "EN2") (class "Default")
      (node (ref "IC5") (pin "5") (pinfunction "I_5") (pintype "input"))
      (node (ref "IC9") (pin "4") (pinfunction "I0_4") (pintype "input"))
      (node (ref "J6") (pin "4") (pinfunction "4_4") (pintype "passive"))
      (node (ref "R26") (pin "2") (pinfunction "2_2") (pintype "passive"))
      (node (ref "TP28") (pin "TP") (pinfunction "TP_TP") (pintype "input"))
    )
    (net (code "4") (name "EN3") (class "Default")
      (node (ref "IC5") (pin "2") (pinfunction "I_2") (pintype "input"))
      (node (ref "IC9") (pin "9") (pinfunction "I0_9") (pintype "input"))
      (node (ref "J6") (pin "6") (pinfunction "6_6") (pintype "passive"))
      (node (ref "R27") (pin "2") (pinfunction "2_2") (pintype "passive"))
      (node (ref "TP29") (pin "TP") (pinfunction "TP_TP") (pintype "input"))
    )
    (net (code "5") (name "FEEDBACK1") (class "Default")
      (node (ref "IC6") (pin "2") (pinfunction "I_2") (pintype "input"))
      (node (ref "J2") (pin "2") (pinfunction "2_2") (pintype "passive"))
    )
    (net (code "6") (name "FEEDBACK2") (class "Default")
      (node (ref "IC6") (pin "5") (pinfunction "I_5") (pintype "input"))
      (node (ref "J3") (pin "2") (pinfunction "2_2") (pintype "passive"))
    )
    (net (code "7") (name "FEEDBACK3") (class "Default")
      (node (ref "IC6") (pin "9") (pinfunction "I_9") (pintype "input"))
      (node (ref "J4") (pin "2") (pinfunction "2_2") (pintype "passive"))
    )
    (net (code "8") (name "GND") (class "Default")
      (node (ref "C10") (pin "2") (pinfunction "2_2") (pintype "passive"))
      (node (ref "C11") (pin "2") (pinfunction "2_2") (pintype "passive"))
      (node (ref "C12") (pin "2") (pinfunction "2_2") (pintype "passive"))
      (node (ref "C13") (pin "2") (pinfunction "2_2") (pintype "passive"))
      (node (ref "C15") (pin "2") (pinfunction "2_2") (pintype "passive"))
      (node (ref "C16") (pin "2") (pinfunction "2_2") (pintype "passive"))
      (node (ref "C17") (pin "-") (pinfunction "-_-") (pintype "passive"))
      (node (ref "C18") (pin "2") (pinfunction "2_2") (pintype "passive"))
      (node (ref "C19") (pin "2") (pinfunction "2_2") (pintype "passive"))
      (node (ref "C2") (pin "-") (pinfunction "-_-") (pintype "passive"))
      (node (ref "C20") (pin "2") (pinfunction "2_2") (pintype "passive"))
      (node (ref "C21") (pin "2") (pinfunction "2_2") (pintype "passive"))
      (node (ref "C22") (pin "2") (pinfunction "2_2") (pintype "passive"))
      (node (ref "C23") (pin "2") (pinfunction "2_2") (pintype "passive"))
      (node (ref "C24") (pin "2") (pinfunction "2_2") (pintype "passive"))
      (node (ref "C25") (pin "2") (pinfunction "2_2") (pintype "passive"))
      (node (ref "C27") (pin "2") (pinfunction "2_2") (pintype "passive"))
      (node (ref "C3") (pin "-") (pinfunction "-_-") (pintype "passive"))
      (node (ref "C5") (pin "-") (pinfunction "-_-") (pintype "passive"))
      (node (ref "C6") (pin "-") (pinfunction "-_-") (pintype "passive"))
      (node (ref "C7") (pin "2") (pinfunction "2_2") (pintype "passive"))
      (node (ref "C8") (pin "2") (pinfunction "2_2") (pintype "passive"))
      (node (ref "D1") (pin "A") (pinfunction "A_A") (pintype "passive"))
      (node (ref "D10") (pin "A") (pinfunction "A_A") (pintype "passive"))
      (node (ref "D12") (pin "A") (pinfunction "A_A") (pintype "passive"))
      (node (ref "D14") (pin "A") (pinfunction "A_A") (pintype "passive"))
      (node (ref "D16") (pin "C") (pinfunction "C_C") (pintype "passive"))
      (node (ref "D17") (pin "C") (pinfunction "C_C") (pintype "passive"))
      (node (ref "D18") (pin "C") (pinfunction "C_C") (pintype "passive"))
      (node (ref "D19") (pin "C") (pinfunction "C_C") (pintype "passive"))
      (node (ref "D20") (pin "C") (pinfunction "C_C") (pintype "passive"))
      (node (ref "D21") (pin "C") (pinfunction "C_C") (pintype "passive"))
      (node (ref "D22") (pin "C") (pinfunction "C_C") (pintype "passive"))
      (node (ref "D23") (pin "C") (pinfunction "C_C") (pintype "passive"))
      (node (ref "D24") (pin "C") (pinfunction "C_C") (pintype "passive"))
      (node (ref "D4") (pin "C") (pinfunction "C_C") (pintype "passive"))
      (node (ref "D7") (pin "C") (pinfunction "C_C") (pintype "passive"))
      (node (ref "D9") (pin "A") (pinfunction "A_A") (pintype "passive"))
      (node (ref "IC1") (pin "2") (pinfunction "GNDSIG_2") (pintype "input"))
      (node (ref "IC1") (pin "4") (pinfunction "GND_4") (pintype "power_in"))
      (node (ref "IC10") (pin "1") (pinfunction "OE_1") (pintype "input"))
      (node (ref "IC10") (pin "10") (pinfunction "OE_10") (pintype "input"))
      (node (ref "IC10") (pin "12") (pinfunction "I_12") (pintype "input"))
      (node (ref "IC10") (pin "13") (pinfunction "OE_13") (pintype "input"))
      (node (ref "IC10") (pin "4") (pinfunction "OE_4") (pintype "input"))
      (node (ref "IC10") (pin "7") (pinfunction "GND_7") (pintype "power_in"))
      (node (ref "IC2") (pin "4") (pinfunction "V-_4") (pintype "power_in"))
      (node (ref "IC3") (pin "4") (pinfunction "V-_4") (pintype "power_in"))
      (node (ref "IC4") (pin "11") (pinfunction "V-_11") (pintype "power_in"))
      (node (ref "IC4") (pin "13") (pinfunction "-IN_13") (pintype "input"))
      (node (ref "IC5") (pin "1") (pinfunction "OE_1") (pintype "input"))
      (node (ref "IC5") (pin "10") (pinfunction "OE_10") (pintype "input"))
      (node (ref "IC5") (pin "12") (pinfunction "I_12") (pintype "input"))
      (node (ref "IC5") (pin "13") (pinfunction "OE_13") (pintype "input"))
      (node (ref "IC5") (pin "4") (pinfunction "OE_4") (pintype "input"))
      (node (ref "IC5") (pin "7") (pinfunction "GND_7") (pintype "power_in"))
      (node (ref "IC6") (pin "1") (pinfunction "OE_1") (pintype "input"))
      (node (ref "IC6") (pin "10") (pinfunction "OE_10") (pintype "input"))
      (node (ref "IC6") (pin "12") (pinfunction "I_12") (pintype "input"))
      (node (ref "IC6") (pin "13") (pinfunction "OE_13") (pintype "input"))
      (node (ref "IC6") (pin "4") (pinfunction "OE_4") (pintype "input"))
      (node (ref "IC6") (pin "7") (pinfunction "GND_7") (pintype "power_in"))
      (node (ref "IC7") (pin "4") (pinfunction "V-_4") (pintype "power_in"))
      (node (ref "IC8") (pin "14") (pinfunction "C_14") (pintype "input"))
      (node (ref "IC8") (pin "8") (pinfunction "GND_8") (pintype "power_in"))
      (node (ref "IC9") (pin "7") (pinfunction "GND_7") (pintype "power_in"))
      (node (ref "J16") (pin "1") (pinfunction "1_1") (pintype "passive"))
      (node (ref "J17") (pin "1") (pinfunction "1_1") (pintype "passive"))
      (node (ref "J18") (pin "1") (pinfunction "1_1") (pintype "passive"))
      (node (ref "J19") (pin "3") (pinfunction "3_3") (pintype "passive"))
      (node (ref "J5") (pin "3") (pinfunction "3_3") (pintype "passive"))
      (node (ref "J5") (pin "4") (pinfunction "4_4") (pintype "passive"))
      (node (ref "J5") (pin "7") (pinfunction "7_7") (pintype "passive"))
      (node (ref "J5") (pin "8") (pinfunction "8_8") (pintype "passive"))
      (node (ref "L1") (pin "3") (pinfunction "4_3") (pintype "passive"))
      (node (ref "R1") (pin "1") (pinfunction "1_1") (pintype "passive"))
      (node (ref "R11") (pin "1") (pinfunction "1_1") (pintype "passive"))
      (node (ref "R12") (pin "1") (pinfunction "1_1") (pintype "passive"))
      (node (ref "R13") (pin "1") (pinfunction "1_1") (pintype "passive"))
      (node (ref "R14") (pin "1") (pinfunction "1_1") (pintype "passive"))
      (node (ref "R16") (pin "3") (pinfunction "E_3") (pintype "passive"))
      (node (ref "R22") (pin "1") (pinfunction "1_1") (pintype "passive"))
      (node (ref "R23") (pin "1") (pinfunction "1_1") (pintype "passive"))
      (node (ref "R24") (pin "1") (pinfunction "1_1") (pintype "passive"))
      (node (ref "R25") (pin "1") (pinfunction "1_1") (pintype "passive"))
      (node (ref "R26") (pin "1") (pinfunction "1_1") (pintype "passive"))
      (node (ref "R27") (pin "1") (pinfunction "1_1") (pintype "passive"))
      (node (ref "R32") (pin "1") (pinfunction "1_1") (pintype "passive"))
      (node (ref "R33") (pin "1") (pinfunction "1_1") (pintype "passive"))
      (node (ref "R34") (pin "1") (pinfunction "1_1") (pintype "passive"))
      (node (ref "R35") (pin "1") (pinfunction "1_1") (pintype "passive"))
      (node (ref "R5") (pin "1") (pinfunction "1_1") (pintype "passive"))
      (node (ref "R8") (pin "1") (pinfunction "1_1") (pintype "passive"))
      (node (ref "TP10") (pin "TP") (pinfunction "TP_TP") (pintype "input"))
      (node (ref "TP17") (pin "TP") (pinfunction "TP_TP") (pintype "input"))
      (node (ref "TP18") (pin "TP") (pinfunction "TP_TP") (pintype "input"))
      (node (ref "TP9") (pin "TP") (pinfunction "TP_TP") (pintype "input"))
      (node (ref "U1") (pin "2") (pinfunction "GND_2") (pintype "bidirectional"))
      (node (ref "U2") (pin "1") (pinfunction "GND_1") (pintype "power_in"))
      (node (ref "U2") (pin "10") (pinfunction "GND_10") (pintype "power_in"))
      (node (ref "U2") (pin "11") (pinfunction "GND_11") (pintype "power_in"))
      (node (ref "U2") (pin "20") (pinfunction "GND_20") (pintype "power_in"))
      (node (ref "U2") (pin "PAD") (pinfunction "GND_PAD") (pintype "power_in"))
      (node (ref "X4") (pin "2") (pinfunction "KL_2") (pintype "passive"))
    )
    (net (code "9") (name "I+") (class "Default")
      (node (ref "R4") (pin "SB") (pinfunction "SB_SB") (pintype "passive"))
      (node (ref "U1") (pin "3") (pinfunction "VIN+_3") (pintype "bidirectional"))
    )
    (net (code "10") (name "I-") (class "Default")
      (node (ref "R4") (pin "SA") (pinfunction "SA_SA") (pintype "passive"))
      (node (ref "U1") (pin "4") (pinfunction "VIN-_4") (pintype "bidirectional"))
    )
    (net (code "11") (name "I_OUT") (class "Default")
      (node (ref "IC2") (pin "2") (pinfunction "-IN_2") (pintype "input"))
      (node (ref "IC2") (pin "6") (pinfunction "OUT_6") (pintype "output"))
      (node (ref "R6") (pin "2") (pinfunction "2_2") (pintype "passive"))
      (node (ref "TP13") (pin "TP") (pinfunction "TP_TP") (pintype "input"))
    )
    (net (code "12") (name "MOTOR_I") (class "Default")
      (node (ref "R11") (pin "2") (pinfunction "2_2") (pintype "passive"))
      (node (ref "R12") (pin "2") (pinfunction "2_2") (pintype "passive"))
      (node (ref "R13") (pin "2") (pinfunction "2_2") (pintype "passive"))
      (node (ref "R14") (pin "2") (pinfunction "2_2") (pintype "passive"))
      (node (ref "R15") (pin "2") (pinfunction "2_2") (pintype "passive"))
      (node (ref "R31") (pin "2") (pinfunction "2_2") (pintype "passive"))
      (node (ref "TP20") (pin "TP") (pinfunction "TP_TP") (pintype "input"))
      (node (ref "U2") (pin "19") (pinfunction "VSENSE2_19") (pintype "output"))
      (node (ref "U2") (pin "2") (pinfunction "VSENSE1_2") (pintype "output"))
    )
    (net (code "13") (name "MOTOR_OC") (class "Default")
      (node (ref "IC8") (pin "13") (pinfunction "Q_13") (pintype "output"))
      (node (ref "R18") (pin "2") (pinfunction "2_2") (pintype "passive"))
    )
    (net (code "14") (name "Net-(C1-Pad+)") (class "Default")
      (node (ref "C1") (pin "+") (pinfunction "+_+") (pintype "passive"))
      (node (ref "L1") (pin "1") (pinfunction "1_1") (pintype "passive"))
      (node (ref "Q1") (pin "S") (pinfunction "S_S") (pintype "passive"))
      (node (ref "R3") (pin "2") (pinfunction "2_2") (pintype "passive"))
      (node (ref "TP2") (pin "TP") (pinfunction "TP_TP") (pintype "input"))
    )
    (net (code "15") (name "Net-(C14-Pad1)") (class "Default")
      (node (ref "C14") (pin "1") (pinfunction "1_1") (pintype "passive"))
      (node (ref "D5") (pin "C") (pinfunction "C_C") (pintype "passive"))
      (node (ref "D6") (pin "A") (pinfunction "A_A") (pintype "passive"))
    )
    (net (code "16") (name "Net-(D2-PadA)") (class "Default")
      (node (ref "D2") (pin "A") (pinfunction "A_A") (pintype "passive"))
      (node (ref "D3") (pin "A") (pinfunction "A_A") (pintype "passive"))
    )
    (net (code "17") (name "Net-(D2-PadC)") (class "Default")
      (node (ref "D2") (pin "C") (pinfunction "C_C") (pintype "passive"))
      (node (ref "Q1") (pin "G") (pinfunction "G_G") (pintype "passive"))
      (node (ref "R2") (pin "2") (pinfunction "2_2") (pintype "passive"))
      (node (ref "R3") (pin "1") (pinfunction "1_1") (pintype "passive"))
      (node (ref "TP12") (pin "TP") (pinfunction "TP_TP") (pintype "input"))
    )
    (net (code "18") (name "Net-(D4-PadA)") (class "Default")
      (node (ref "D4") (pin "A") (pinfunction "A_A") (pintype "passive"))
      (node (ref "R10") (pin "1") (pinfunction "1_1") (pintype "passive"))
    )
    (net (code "19") (name "Net-(D7-PadA)") (class "Default")
      (node (ref "D7") (pin "A") (pinfunction "A_A") (pintype "passive"))
      (node (ref "R18") (pin "1") (pinfunction "1_1") (pintype "passive"))
    )
    (net (code "20") (name "Net-(D8-PadA)") (class "Default")
      (node (ref "D8") (pin "A") (pinfunction "A_A") (pintype "passive"))
      (node (ref "D9") (pin "C") (pinfunction "C_C") (pintype "passive"))
      (node (ref "J6") (pin "8") (pinfunction "8_8") (pintype "passive"))
      (node (ref "R31") (pin "1") (pinfunction "1_1") (pintype "passive"))
      (node (ref "R32") (pin "2") (pinfunction "2_2") (pintype "passive"))
    )
    (net (code "21") (name "Net-(D16-PadA)") (class "Default")
      (node (ref "D16") (pin "A") (pinfunction "A_A") (pintype "passive"))
      (node (ref "R39") (pin "2") (pinfunction "2_2") (pintype "passive"))
    )
    (net (code "22") (name "Net-(D17-PadA)") (class "Default")
      (node (ref "D17") (pin "A") (pinfunction "A_A") (pintype "passive"))
      (node (ref "R40") (pin "2") (pinfunction "2_2") (pintype "passive"))
    )
    (net (code "23") (name "Net-(D18-PadA)") (class "Default")
      (node (ref "D18") (pin "A") (pinfunction "A_A") (pintype "passive"))
      (node (ref "R41") (pin "2") (pinfunction "2_2") (pintype "passive"))
    )
    (net (code "24") (name "Net-(D19-PadA)") (class "Default")
      (node (ref "D19") (pin "A") (pinfunction "A_A") (pintype "passive"))
      (node (ref "R42") (pin "2") (pinfunction "2_2") (pintype "passive"))
    )
    (net (code "25") (name "Net-(D20-PadA)") (class "Default")
      (node (ref "D20") (pin "A") (pinfunction "A_A") (pintype "passive"))
      (node (ref "R43") (pin "2") (pinfunction "2_2") (pintype "passive"))
    )
    (net (code "26") (name "Net-(D21-PadA)") (class "Default")
      (node (ref "D21") (pin "A") (pinfunction "A_A") (pintype "passive"))
      (node (ref "R44") (pin "2") (pinfunction "2_2") (pintype "passive"))
    )
    (net (code "27") (name "Net-(D22-PadA)") (class "Default")
      (node (ref "D22") (pin "A") (pinfunction "A_A") (pintype "passive"))
      (node (ref "R46") (pin "1") (pinfunction "1_1") (pintype "passive"))
    )
    (net (code "28") (name "Net-(D23-PadA)") (class "Default")
      (node (ref "D23") (pin "A") (pinfunction "A_A") (pintype "passive"))
      (node (ref "R47") (pin "1") (pinfunction "1_1") (pintype "passive"))
    )
    (net (code "29") (name "Net-(D24-PadA)") (class "Default")
      (node (ref "D24") (pin "A") (pinfunction "A_A") (pintype "passive"))
      (node (ref "R48") (pin "1") (pinfunction "1_1") (pintype "passive"))
    )
    (net (code "30") (name "Net-(F1-Pad2A)") (class "Default")
      (node (ref "F1") (pin "2A") (pinfunction "2A_2A") (pintype "passive"))
      (node (ref "Q1") (pin "D") (pinfunction "D_D") (pintype "passive"))
    )
    (net (code "31") (name "Net-(IC1-FB)") (class "Default")
      (node (ref "C5") (pin "+") (pinfunction "+_+") (pintype "passive"))
      (node (ref "IC1") (pin "1") (pinfunction "FB_1") (pintype "input"))
      (node (ref "L3") (pin "1") (pinfunction "1_1") (pintype "passive"))
      (node (ref "L4") (pin "2") (pinfunction "2_2") (pintype "passive"))
    )
    (net (code "32") (name "Net-(IC1-OUT)") (class "Default")
      (node (ref "D1") (pin "C") (pinfunction "C_C") (pintype "passive"))
      (node (ref "IC1") (pin "7") (pinfunction "OUT_7") (pintype "passive"))
      (node (ref "L3") (pin "2") (pinfunction "2_2") (pintype "passive"))
    )
    (net (code "33") (name "Net-(IC1-~{ON{slash}OFF})") (class "Default")
      (node (ref "C4") (pin "2") (pinfunction "2_2") (pintype "passive"))
      (node (ref "IC1") (pin "3") (pinfunction "~{ON/OFF}_3") (pintype "input"))
      (node (ref "R1") (pin "2") (pinfunction "2_2") (pintype "passive"))
    )
    (net (code "34") (name "Net-(IC2-+IN)") (class "Default")
      (node (ref "C7") (pin "1") (pinfunction "1_1") (pintype "passive"))
      (node (ref "IC2") (pin "3") (pinfunction "+IN_3") (pintype "input"))
      (node (ref "R5") (pin "2") (pinfunction "2_2") (pintype "passive"))
      (node (ref "TP16") (pin "TP") (pinfunction "TP_TP") (pintype "input"))
      (node (ref "U1") (pin "1") (pinfunction "OUT_1") (pintype "bidirectional"))
    )
    (net (code "35") (name "Net-(IC3-+IN)") (class "Default")
      (node (ref "C8") (pin "1") (pinfunction "1_1") (pintype "passive"))
      (node (ref "IC3") (pin "3") (pinfunction "+IN_3") (pintype "input"))
      (node (ref "R7") (pin "1") (pinfunction "1_1") (pintype "passive"))
      (node (ref "R8") (pin "2") (pinfunction "2_2") (pintype "passive"))
      (node (ref "TP15") (pin "TP") (pinfunction "TP_TP") (pintype "input"))
    )
    (net (code "36") (name "Net-(IC4A-+IN)") (class "Default")
      (node (ref "D10") (pin "C") (pinfunction "C_C") (pintype "passive"))
      (node (ref "D11") (pin "A") (pinfunction "A_A") (pintype "passive"))
      (node (ref "IC4") (pin "3") (pinfunction "+IN_3") (pintype "input"))
      (node (ref "R19") (pin "1") (pinfunction "1_1") (pintype "passive"))
      (node (ref "R35") (pin "2") (pinfunction "2_2") (pintype "passive"))
      (node (ref "R36") (pin "2") (pinfunction "2_2") (pintype "passive"))
      (node (ref "TP33") (pin "TP") (pinfunction "TP_TP") (pintype "input"))
    )
    (net (code "37") (name "Net-(IC4A--IN)") (class "Default")
      (node (ref "IC4") (pin "2") (pinfunction "-IN_2") (pintype "input"))
      (node (ref "IC4") (pin "6") (pinfunction "-IN_6") (pintype "input"))
      (node (ref "IC4") (pin "9") (pinfunction "-IN_9") (pintype "input"))
      (node (ref "R36") (pin "1") (pinfunction "1_1") (pintype "passive"))
      (node (ref "R37") (pin "1") (pinfunction "1_1") (pintype "passive"))
      (node (ref "R38") (pin "1") (pinfunction "1_1") (pintype "passive"))
      (node (ref "TP36") (pin "TP") (pinfunction "TP_TP") (pintype "input"))
    )
    (net (code "38") (name "Net-(IC4A-OUT)") (class "Default")
      (node (ref "IC4") (pin "1") (pinfunction "OUT_1") (pintype "output"))
      (node (ref "J2") (pin "1") (pinfunction "1_1") (pintype "passive"))
    )
    (net (code "39") (name "Net-(IC4B-+IN)") (class "Default")
      (node (ref "D12") (pin "C") (pinfunction "C_C") (pintype "passive"))
      (node (ref "D13") (pin "A") (pinfunction "A_A") (pintype "passive"))
      (node (ref "IC4") (pin "5") (pinfunction "+IN_5") (pintype "input"))
      (node (ref "R20") (pin "1") (pinfunction "1_1") (pintype "passive"))
      (node (ref "R34") (pin "2") (pinfunction "2_2") (pintype "passive"))
      (node (ref "R37") (pin "2") (pinfunction "2_2") (pintype "passive"))
      (node (ref "TP34") (pin "TP") (pinfunction "TP_TP") (pintype "input"))
    )
    (net (code "40") (name "Net-(IC4B-OUT)") (class "Default")
      (node (ref "IC4") (pin "7") (pinfunction "OUT_7") (pintype "output"))
      (node (ref "J3") (pin "1") (pinfunction "1_1") (pintype "passive"))
    )
    (net (code "41") (name "Net-(IC4C-+IN)") (class "Default")
      (node (ref "D14") (pin "C") (pinfunction "C_C") (pintype "passive"))
      (node (ref "D15") (pin "A") (pinfunction "A_A") (pintype "passive"))
      (node (ref "IC4") (pin "10") (pinfunction "+IN_10") (pintype "input"))
      (node (ref "R21") (pin "1") (pinfunction "1_1") (pintype "passive"))
      (node (ref "R33") (pin "2") (pinfunction "2_2") (pintype "passive"))
      (node (ref "R38") (pin "2") (pinfunction "2_2") (pintype "passive"))
      (node (ref "TP35") (pin "TP") (pinfunction "TP_TP") (pintype "input"))
    )
    (net (code "42") (name "Net-(IC4C-OUT)") (class "Default")
      (node (ref "IC4") (pin "8") (pinfunction "OUT_8") (pintype "output"))
      (node (ref "J4") (pin "1") (pinfunction "1_1") (pintype "passive"))
    )
    (net (code "43") (name "Net-(IC5A-O)") (class "Default")
      (node (ref "IC5") (pin "3") (pinfunction "O_3") (pintype "tri_state"))
      (node (ref "R42") (pin "1") (pinfunction "1_1") (pintype "passive"))
    )
    (net (code "44") (name "Net-(IC5B-O)") (class "Default")
      (node (ref "IC5") (pin "6") (pinfunction "O_6") (pintype "tri_state"))
      (node (ref "R43") (pin "1") (pinfunction "1_1") (pintype "passive"))
    )
    (net (code "45") (name "Net-(IC5C-O)") (class "Default")
      (node (ref "IC5") (pin "8") (pinfunction "O_8") (pintype "tri_state"))
      (node (ref "R44") (pin "1") (pinfunction "1_1") (pintype "passive"))
    )
    (net (code "46") (name "Net-(IC6A-O)") (class "Default")
      (node (ref "IC6") (pin "3") (pinfunction "O_3") (pintype "tri_state"))
      (node (ref "R46") (pin "2") (pinfunction "2_2") (pintype "passive"))
      (node (ref "R51") (pin "1") (pinfunction "1_1") (pintype "passive"))
      (node (ref "TP40") (pin "TP") (pinfunction "TP_TP") (pintype "input"))
    )
    (net (code "47") (name "Net-(IC6B-O)") (class "Default")
      (node (ref "IC6") (pin "6") (pinfunction "O_6") (pintype "tri_state"))
      (node (ref "R47") (pin "2") (pinfunction "2_2") (pintype "passive"))
      (node (ref "R50") (pin "1") (pinfunction "1_1") (pintype "passive"))
      (node (ref "TP41") (pin "TP") (pinfunction "TP_TP") (pintype "input"))
    )
    (net (code "48") (name "Net-(IC6C-O)") (class "Default")
      (node (ref "IC6") (pin "8") (pinfunction "O_8") (pintype "tri_state"))
      (node (ref "R48") (pin "2") (pinfunction "2_2") (pintype "passive"))
      (node (ref "R49") (pin "1") (pinfunction "1_1") (pintype "passive"))
      (node (ref "TP42") (pin "TP") (pinfunction "TP_TP") (pintype "input"))
    )
    (net (code "49") (name "Net-(IC7-+IN)") (class "Default")
      (node (ref "IC7") (pin "3") (pinfunction "+IN_3") (pintype "input"))
      (node (ref "R16") (pin "2") (pinfunction "S_2") (pintype "passive"))
      (node (ref "TP19") (pin "TP") (pinfunction "TP_TP") (pintype "input"))
    )
    (net (code "50") (name "Net-(IC7--IN)") (class "Default")
      (node (ref "C16") (pin "1") (pinfunction "1_1") (pintype "passive"))
      (node (ref "IC7") (pin "2") (pinfunction "-IN_2") (pintype "input"))
      (node (ref "R15") (pin "1") (pinfunction "1_1") (pintype "passive"))
      (node (ref "TP8") (pin "TP") (pinfunction "TP_TP") (pintype "input"))
    )
    (net (code "51") (name "Net-(IC7-OUT)") (class "Default")
      (node (ref "IC7") (pin "6") (pinfunction "OUT_6") (pintype "output"))
      (node (ref "IC8") (pin "2") (pinfunction "B_2") (pintype "input"))
      (node (ref "TP21") (pin "TP") (pinfunction "TP_TP") (pintype "input"))
    )
    (net (code "52") (name "Net-(IC8A-CLR)") (class "Default")
      (node (ref "IC8") (pin "3") (pinfunction "CLR_3") (pintype "input"))
      (node (ref "J19") (pin "2") (pinfunction "2_2") (pintype "passive"))
    )
    (net (code "53") (name "Net-(IC8A-R{slash}C)") (class "Default")
      (node (ref "C18") (pin "1") (pinfunction "1_1") (pintype "passive"))
      (node (ref "IC8") (pin "15") (pinfunction "R/C_15") (pintype "input"))
      (node (ref "R17") (pin "1") (pinfunction "1_1") (pintype "passive"))
    )
    (net (code "54") (name "Net-(IC8A-~{Q})") (class "Default")
      (node (ref "IC8") (pin "4") (pinfunction "~{Q}_4") (pintype "output"))
      (node (ref "IC9") (pin "10") (pinfunction "I1_10") (pintype "input"))
      (node (ref "IC9") (pin "2") (pinfunction "I1_2") (pintype "input"))
      (node (ref "IC9") (pin "5") (pinfunction "I1_5") (pintype "input"))
      (node (ref "TP22") (pin "TP") (pinfunction "TP_TP") (pintype "input"))
    )
    (net (code "55") (name "Net-(IC9A-O)") (class "Default")
      (node (ref "IC9") (pin "3") (pinfunction "O_3") (pintype "output"))
      (node (ref "U2") (pin "8") (pinfunction "EN1_8") (pintype "input"))
    )
    (net (code "56") (name "Net-(IC9B-O)") (class "Default")
      (node (ref "IC9") (pin "6") (pinfunction "O_6") (pintype "output"))
      (node (ref "U2") (pin "3") (pinfunction "EN2_3") (pintype "input"))
    )
    (net (code "57") (name "Net-(IC9C-O)") (class "Default")
      (node (ref "IC9") (pin "8") (pinfunction "O_8") (pintype "output"))
      (node (ref "U2") (pin "13") (pinfunction "EN3_13") (pintype "input"))
    )
    (net (code "58") (name "Net-(IC10A-O)") (class "Default")
      (node (ref "IC10") (pin "3") (pinfunction "O_3") (pintype "tri_state"))
      (node (ref "R39") (pin "1") (pinfunction "1_1") (pintype "passive"))
    )
    (net (code "59") (name "Net-(IC10B-O)") (class "Default")
      (node (ref "IC10") (pin "6") (pinfunction "O_6") (pintype "tri_state"))
      (node (ref "R40") (pin "1") (pinfunction "1_1") (pintype "passive"))
    )
    (net (code "60") (name "Net-(IC10C-O)") (class "Default")
      (node (ref "IC10") (pin "8") (pinfunction "O_8") (pintype "tri_state"))
      (node (ref "R41") (pin "1") (pinfunction "1_1") (pintype "passive"))
    )
    (net (code "61") (name "Net-(J5-Pad9)") (class "Default")
      (node (ref "J5") (pin "9") (pinfunction "9_9") (pintype "passive"))
      (node (ref "R6") (pin "1") (pinfunction "1_1") (pintype "passive"))
    )
    (net (code "62") (name "Net-(J5-Pad10)") (class "Default")
      (node (ref "J5") (pin "10") (pinfunction "10_10") (pintype "passive"))
      (node (ref "R9") (pin "1") (pinfunction "1_1") (pintype "passive"))
    )
    (net (code "63") (name "Net-(J6-Pad7)") (class "Default")
      (node (ref "J6") (pin "7") (pinfunction "7_7") (pintype "passive"))
      (node (ref "R51") (pin "2") (pinfunction "2_2") (pintype "passive"))
    )
    (net (code "64") (name "Net-(J6-Pad9)") (class "Default")
      (node (ref "J6") (pin "9") (pinfunction "9_9") (pintype "passive"))
      (node (ref "R50") (pin "2") (pinfunction "2_2") (pintype "passive"))
    )
    (net (code "65") (name "Net-(J6-Pad10)") (class "Default")
      (node (ref "J6") (pin "10") (pinfunction "10_10") (pintype "passive"))
      (node (ref "R49") (pin "2") (pinfunction "2_2") (pintype "passive"))
    )
    (net (code "66") (name "Net-(L1-2)") (class "Default")
      (node (ref "C2") (pin "+") (pinfunction "+_+") (pintype "passive"))
      (node (ref "L1") (pin "4") (pinfunction "2_4") (pintype "passive"))
      (node (ref "R4") (pin "B") (pinfunction "B_B") (pintype "passive"))
      (node (ref "TP4") (pin "TP") (pinfunction "TP_TP") (pintype "input"))
    )
    (net (code "67") (name "Net-(L1-3)") (class "Default")
      (node (ref "C1") (pin "-") (pinfunction "-_-") (pintype "passive"))
      (node (ref "D3") (pin "C") (pinfunction "C_C") (pintype "passive"))
      (node (ref "J1") (pin "GND") (pinfunction "GND_GND") (pintype "bidirectional"))
      (node (ref "J1") (pin "GNDBREAK") (pinfunction "GNDBREAK_GNDBREAK") (pintype "bidirectional"))
      (node (ref "L1") (pin "2") (pinfunction "3_2") (pintype "passive"))
      (node (ref "R2") (pin "1") (pinfunction "1_1") (pintype "passive"))
      (node (ref "TP3") (pin "TP") (pinfunction "TP_TP") (pintype "input"))
      (node (ref "TP7") (pin "TP") (pinfunction "TP_TP") (pintype "input"))
      (node (ref "X1") (pin "1") (pinfunction "KL_1") (pintype "passive"))
    )
    (net (code "68") (name "Net-(R16-A)") (class "Default")
      (node (ref "R16") (pin "1") (pinfunction "A_1") (pintype "passive"))
      (node (ref "R45") (pin "1") (pinfunction "1_1") (pintype "passive"))
    )
    (net (code "69") (name "Net-(U2-VBOOT)") (class "Default")
      (node (ref "C15") (pin "1") (pinfunction "1_1") (pintype "passive"))
      (node (ref "D6") (pin "C") (pinfunction "C_C") (pintype "passive"))
      (node (ref "TP23") (pin "TP") (pinfunction "TP_TP") (pintype "input"))
      (node (ref "U2") (pin "18") (pinfunction "VBOOT_18") (pintype "output"))
    )
    (net (code "70") (name "Net-(U2-VCP)") (class "Default")
      (node (ref "C14") (pin "2") (pinfunction "2_2") (pintype "passive"))
      (node (ref "U2") (pin "17") (pinfunction "VCP_17") (pintype "input"))
    )
    (net (code "71") (name "Net-(U2-VREF)") (class "Default")
      (node (ref "C17") (pin "+") (pinfunction "+_+") (pintype "passive"))
      (node (ref "U2") (pin "16") (pinfunction "VREF_16") (pintype "output"))
    )
    (net (code "72") (name "Net-(X3A-KL)") (class "Default")
      (node (ref "J2") (pin "3") (pinfunction "3_3") (pintype "passive"))
      (node (ref "R54") (pin "1") (pinfunction "1_1") (pintype "passive"))
      (node (ref "TP37") (pin "TP") (pinfunction "TP_TP") (pintype "input"))
      (node (ref "X3") (pin "1") (pinfunction "KL_1") (pintype "passive"))
    )
    (net (code "73") (name "Net-(X3B-KL)") (class "Default")
      (node (ref "J3") (pin "3") (pinfunction "3_3") (pintype "passive"))
      (node (ref "R53") (pin "1") (pinfunction "1_1") (pintype "passive"))
      (node (ref "TP38") (pin "TP") (pinfunction "TP_TP") (pintype "input"))
      (node (ref "X3") (pin "2") (pinfunction "KL_2") (pintype "passive"))
    )
    (net (code "74") (name "Net-(X3C-KL)") (class "Default")
      (node (ref "J4") (pin "3") (pinfunction "3_3") (pintype "passive"))
      (node (ref "R52") (pin "1") (pinfunction "1_1") (pintype "passive"))
      (node (ref "TP39") (pin "TP") (pinfunction "TP_TP") (pintype "input"))
      (node (ref "X3") (pin "3") (pinfunction "KL_3") (pintype "passive"))
    )
    (net (code "75") (name "PHASE_A") (class "Default")
      (node (ref "J11") (pin "1") (pinfunction "1_1") (pintype "passive"))
      (node (ref "J12") (pin "1") (pinfunction "1_1") (pintype "passive"))
      (node (ref "R19") (pin "2") (pinfunction "2_2") (pintype "passive"))
      (node (ref "TP24") (pin "TP") (pinfunction "TP_TP") (pintype "input"))
      (node (ref "U2") (pin "6") (pinfunction "OUT1_6") (pintype "output"))
      (node (ref "X2") (pin "1") (pinfunction "KL_1") (pintype "passive"))
    )
    (net (code "76") (name "PHASE_B") (class "Default")
      (node (ref "J10") (pin "1") (pinfunction "1_1") (pintype "passive"))
      (node (ref "J9") (pin "1") (pinfunction "1_1") (pintype "passive"))
      (node (ref "R20") (pin "2") (pinfunction "2_2") (pintype "passive"))
      (node (ref "TP25") (pin "TP") (pinfunction "TP_TP") (pintype "input"))
      (node (ref "U2") (pin "5") (pinfunction "OUT2_5") (pintype "output"))
      (node (ref "X2") (pin "2") (pinfunction "KL_2") (pintype "passive"))
    )
    (net (code "77") (name "PHASE_C") (class "Default")
      (node (ref "J7") (pin "1") (pinfunction "1_1") (pintype "passive"))
      (node (ref "J8") (pin "1") (pinfunction "1_1") (pintype "passive"))
      (node (ref "R21") (pin "2") (pinfunction "2_2") (pintype "passive"))
      (node (ref "TP26") (pin "TP") (pinfunction "TP_TP") (pintype "input"))
      (node (ref "U2") (pin "15") (pinfunction "OUT3_15") (pintype "output"))
      (node (ref "X2") (pin "3") (pinfunction "KL_3") (pintype "passive"))
    )
    (net (code "78") (name "PWM1") (class "Default")
      (node (ref "IC10") (pin "9") (pinfunction "I_9") (pintype "input"))
      (node (ref "J20") (pin "1") (pinfunction "1_1") (pintype "passive"))
      (node (ref "J21") (pin "1") (pinfunction "1_1") (pintype "passive"))
      (node (ref "J6") (pin "1") (pinfunction "1_1") (pintype "passive"))
      (node (ref "R24") (pin "2") (pinfunction "2_2") (pintype "passive"))
      (node (ref "TP30") (pin "TP") (pinfunction "TP_TP") (pintype "input"))
      (node (ref "U2") (pin "7") (pinfunction "IN1_7") (pintype "input"))
    )
    (net (code "79") (name "PWM2") (class "Default")
      (node (ref "IC10") (pin "5") (pinfunction "I_5") (pintype "input"))
      (node (ref "J20") (pin "2") (pinfunction "2_2") (pintype "passive"))
      (node (ref "J6") (pin "3") (pinfunction "3_3") (pintype "passive"))
      (node (ref "R23") (pin "2") (pinfunction "2_2") (pintype "passive"))
      (node (ref "TP31") (pin "TP") (pinfunction "TP_TP") (pintype "input"))
      (node (ref "U2") (pin "4") (pinfunction "IN2_4") (pintype "input"))
    )
    (net (code "80") (name "PWM3") (class "Default")
      (node (ref "IC10") (pin "2") (pinfunction "I_2") (pintype "input"))
      (node (ref "J21") (pin "2") (pinfunction "2_2") (pintype "passive"))
      (node (ref "J6") (pin "5") (pinfunction "5_5") (pintype "passive"))
      (node (ref "R22") (pin "2") (pinfunction "2_2") (pintype "passive"))
      (node (ref "TP32") (pin "TP") (pinfunction "TP_TP") (pintype "input"))
      (node (ref "U2") (pin "14") (pinfunction "IN3_14") (pintype "input"))
    )
    (net (code "81") (name "SUPPLY_MOTOR") (class "Default")
      (node (ref "C22") (pin "1") (pinfunction "1_1") (pintype "passive"))
      (node (ref "C3") (pin "+") (pinfunction "+_+") (pintype "passive"))
      (node (ref "D5") (pin "A") (pinfunction "A_A") (pintype "passive"))
      (node (ref "J13") (pin "1") (pinfunction "1_1") (pintype "passive"))
      (node (ref "J14") (pin "1") (pinfunction "1_1") (pintype "passive"))
      (node (ref "J15") (pin "1") (pinfunction "1_1") (pintype "passive"))
      (node (ref "L2") (pin "2") (pinfunction "2_2") (pintype "passive"))
      (node (ref "TP6") (pin "TP") (pinfunction "TP_TP") (pintype "input"))
      (node (ref "U2") (pin "12") (pinfunction "VS_12") (pintype "power_in"))
      (node (ref "U2") (pin "9") (pinfunction "VS_9") (pintype "power_in"))
    )
    (net (code "82") (name "V+") (class "Default")
      (node (ref "C4") (pin "1") (pinfunction "1_1") (pintype "passive"))
      (node (ref "IC1") (pin "5") (pinfunction "IN_5") (pintype "input"))
      (node (ref "J5") (pin "1") (pinfunction "1_1") (pintype "passive"))
      (node (ref "J5") (pin "2") (pinfunction "2_2") (pintype "passive"))
      (node (ref "L2") (pin "1") (pinfunction "1_1") (pintype "passive"))
      (node (ref "R4") (pin "A") (pinfunction "A_A") (pintype "passive"))
      (node (ref "R7") (pin "2") (pinfunction "2_2") (pintype "passive"))
      (node (ref "TP5") (pin "TP") (pinfunction "TP_TP") (pintype "input"))
    )
    (net (code "83") (name "VIN_+") (class "Default")
      (node (ref "F1") (pin "1A") (pinfunction "1A_1A") (pintype "passive"))
      (node (ref "J1") (pin "PWR") (pinfunction "PWR_PWR") (pintype "bidirectional"))
      (node (ref "TP1") (pin "TP") (pinfunction "TP_TP") (pintype "input"))
      (node (ref "X1") (pin "2") (pinfunction "KL_2") (pintype "passive"))
    )
    (net (code "84") (name "V_OUT") (class "Default")
      (node (ref "IC3") (pin "2") (pinfunction "-IN_2") (pintype "input"))
      (node (ref "IC3") (pin "6") (pinfunction "OUT_6") (pintype "output"))
      (node (ref "R9") (pin "2") (pinfunction "2_2") (pintype "passive"))
      (node (ref "TP14") (pin "TP") (pinfunction "TP_TP") (pintype "input"))
    )
    (net (code "85") (name "unconnected-(F1-Pad1B)") (class "Default")
      (node (ref "F1") (pin "1B") (pinfunction "1B_1B") (pintype "passive"))
    )
    (net (code "86") (name "unconnected-(F1-Pad2B)") (class "Default")
      (node (ref "F1") (pin "2B") (pinfunction "2B_2B") (pintype "passive"))
    )
    (net (code "87") (name "unconnected-(IC4D-OUT-Pad14)") (class "Default")
      (node (ref "IC4") (pin "14") (pinfunction "OUT_14") (pintype "output"))
    )
    (net (code "88") (name "unconnected-(IC5D-O-Pad11)") (class "Default")
      (node (ref "IC5") (pin "11") (pinfunction "O_11") (pintype "tri_state"))
    )
    (net (code "89") (name "unconnected-(IC6D-O-Pad11)") (class "Default")
      (node (ref "IC6") (pin "11") (pinfunction "O_11") (pintype "tri_state"))
    )
    (net (code "90") (name "unconnected-(IC10D-O-Pad11)") (class "Default")
      (node (ref "IC10") (pin "11") (pinfunction "O_11") (pintype "tri_state"))
    )
  )
)
